# icl7109-rp2040-precision-meter_2025-05-1.net
KiCad netlist of a schematic drawn in EasyEDA Pro
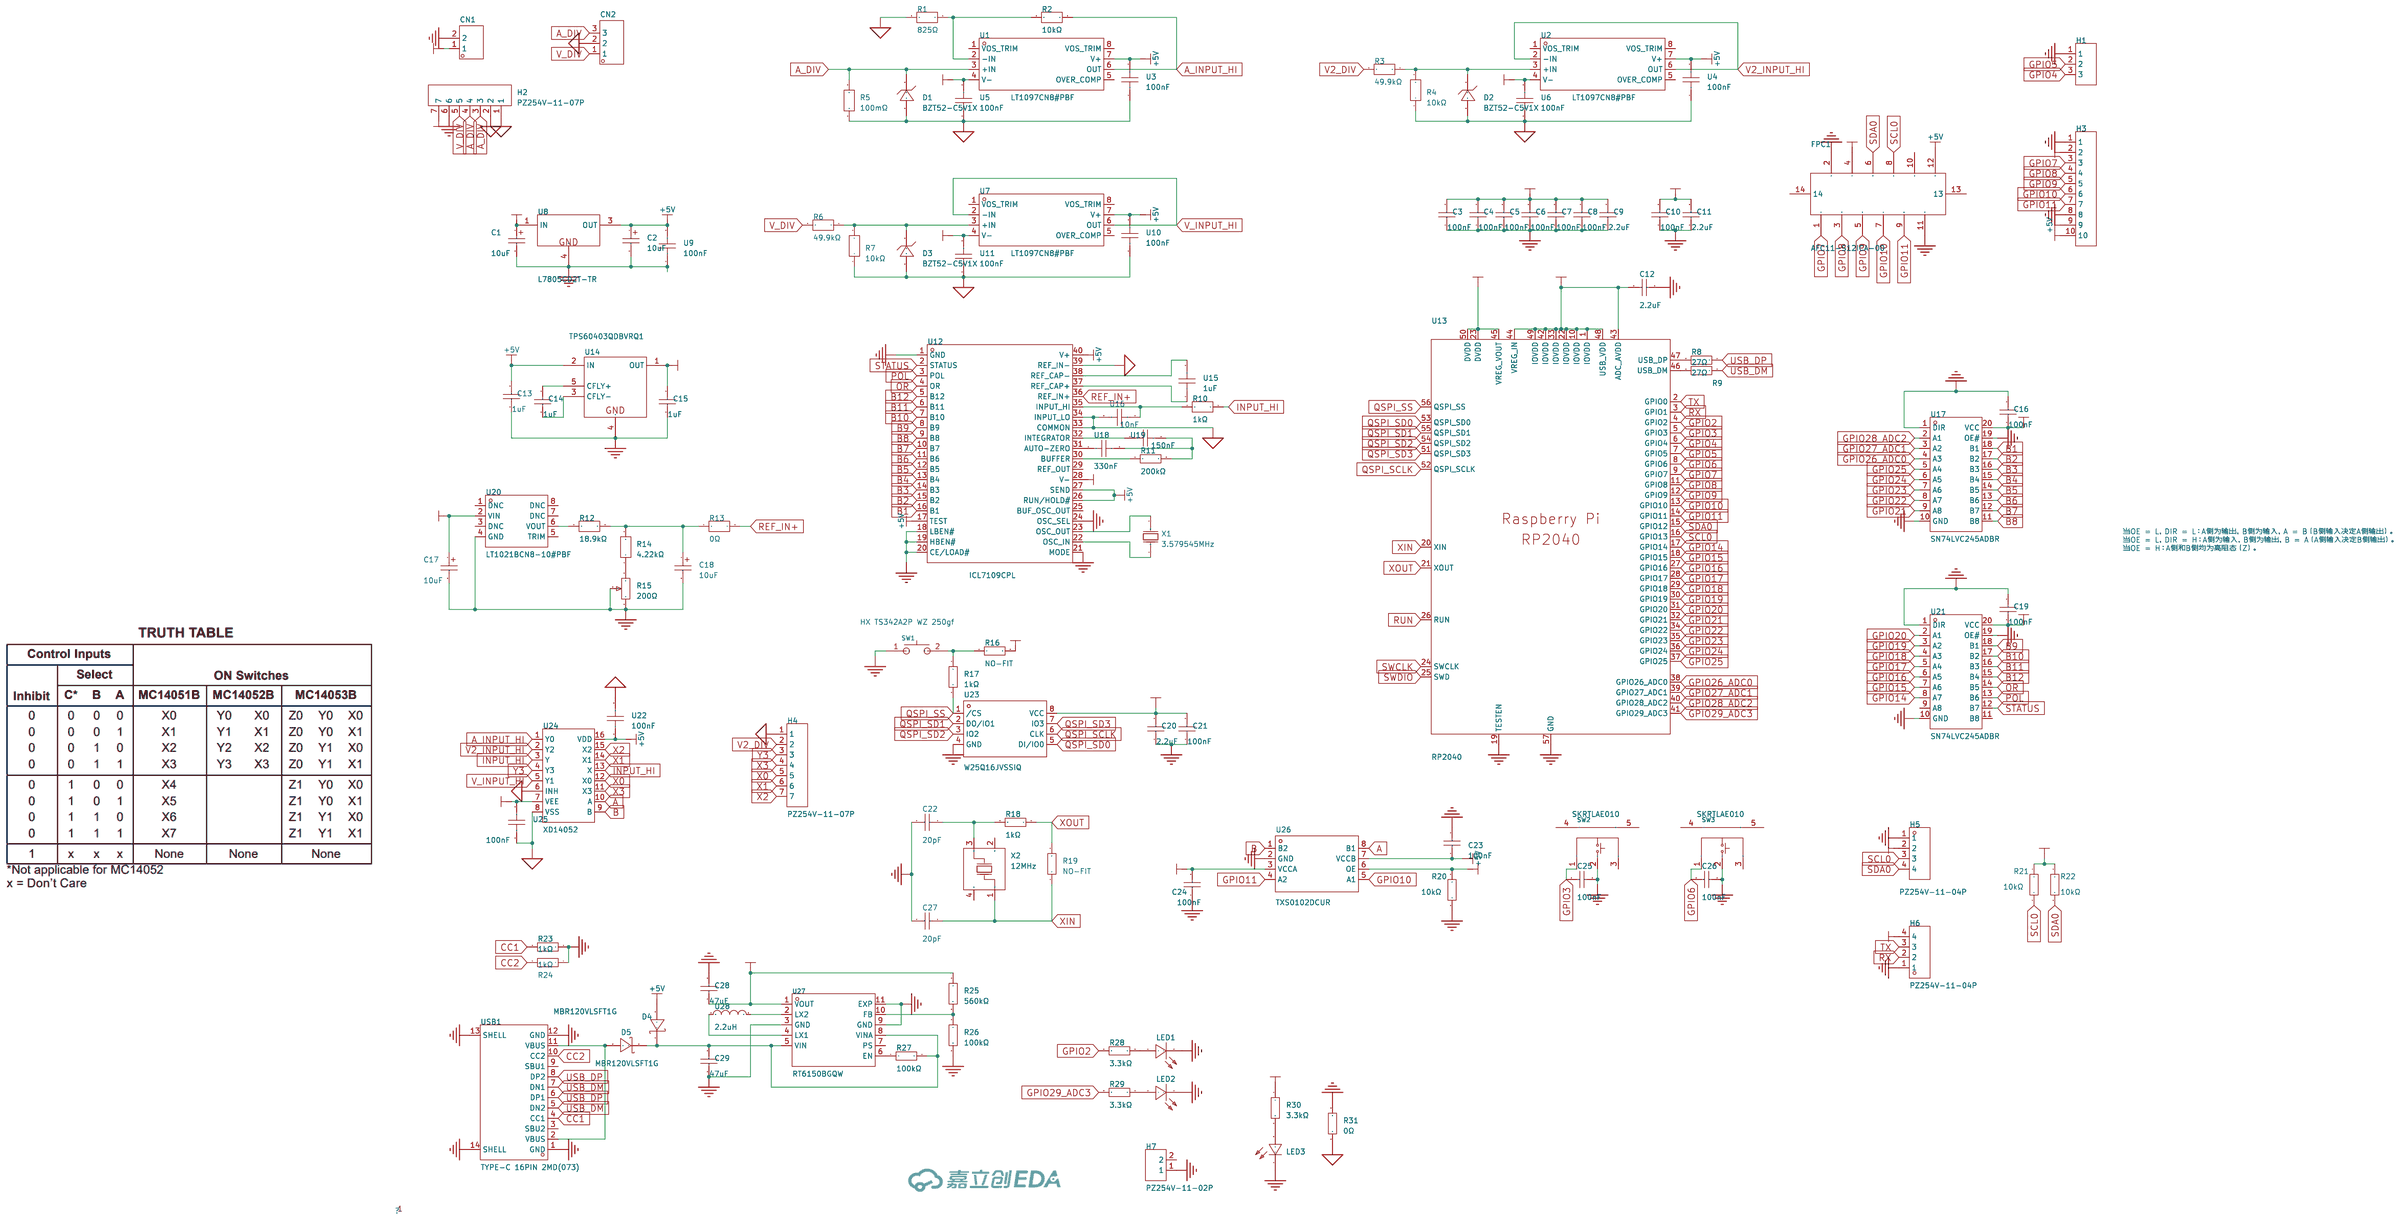
[diagram p0: schematic sheet]

(export (version "E")
  (design (tool "Eeschema 10.0.6"))
  (components
    (comp (ref "C1")
      (value "10uF")
      (footprint "easyedapro:CAP-SMD_L7.3-W4.3-FD")
      (description "容值:47uF;精度:±10%;额定电压:35V;等效串联电阻:600mΩ@100kHz;")
      (fields (field (name "Manufacturer Part") "T491X476K035AT") (field (name "Manufacturer") "KEMET(基美)"))
      (libsource (lib "easyedapro") (part "T491X476K035AT"))
    )
    (comp (ref "C2")
      (value "10uF")
      (footprint "easyedapro:case-b_3528")
      (description "容值:10uF;精度:±10%;额定电压:25V;等效串联电阻:2Ω@100kHz;")
      (fields (field (name "Manufacturer Part") "T491B106K025AT") (field (name "Manufacturer") "KEMET(基美)"))
      (libsource (lib "easyedapro") (part "T491B106K025AT"))
    )
    (comp (ref "C3")
      (value "100nF")
      (footprint "easyedapro:C0805")
      (description "容值:100nF;精度:±10%;额定电压:50V;材质(温度系数):X7R;")
      (fields
        (field (name "Manufacturer Part") "CC0805KRX7R9BB104")
        (field (name "Manufacturer") "YAGEO(国巨)")
      )
      (libsource (lib "easyedapro") (part "CC0805KRX7R9BB104"))
    )
    (comp (ref "C4")
      (value "100nF")
      (footprint "easyedapro:C0805")
      (description "容值:100nF;精度:±10%;额定电压:50V;材质(温度系数):X7R;")
      (fields
        (field (name "Manufacturer Part") "CC0805KRX7R9BB104")
        (field (name "Manufacturer") "YAGEO(国巨)")
      )
      (libsource (lib "easyedapro") (part "CC0805KRX7R9BB104"))
    )
    (comp (ref "C5")
      (value "100nF")
      (footprint "easyedapro:C0805")
      (description "容值:100nF;精度:±10%;额定电压:50V;材质(温度系数):X7R;")
      (fields
        (field (name "Manufacturer Part") "CC0805KRX7R9BB104")
        (field (name "Manufacturer") "YAGEO(国巨)")
      )
      (libsource (lib "easyedapro") (part "CC0805KRX7R9BB104"))
    )
    (comp (ref "C6")
      (value "100nF")
      (footprint "easyedapro:C0805")
      (description "容值:100nF;精度:±10%;额定电压:50V;材质(温度系数):X7R;")
      (fields
        (field (name "Manufacturer Part") "CC0805KRX7R9BB104")
        (field (name "Manufacturer") "YAGEO(国巨)")
      )
      (libsource (lib "easyedapro") (part "CC0805KRX7R9BB104"))
    )
    (comp (ref "C7")
      (value "100nF")
      (footprint "easyedapro:C0805")
      (description "容值:100nF;精度:±10%;额定电压:50V;材质(温度系数):X7R;")
      (fields
        (field (name "Manufacturer Part") "CC0805KRX7R9BB104")
        (field (name "Manufacturer") "YAGEO(国巨)")
      )
      (libsource (lib "easyedapro") (part "CC0805KRX7R9BB104"))
    )
    (comp (ref "C8")
      (value "100nF")
      (footprint "easyedapro:C0805")
      (description "容值:100nF;精度:±10%;额定电压:50V;材质(温度系数):X7R;")
      (fields
        (field (name "Manufacturer Part") "CC0805KRX7R9BB104")
        (field (name "Manufacturer") "YAGEO(国巨)")
      )
      (libsource (lib "easyedapro") (part "CC0805KRX7R9BB104"))
    )
    (comp (ref "C9")
      (value "2.2uF")
      (footprint "easyedapro:C0805")
      (description "容值:100nF;精度:±10%;额定电压:50V;材质(温度系数):X7R;")
      (fields
        (field (name "Manufacturer Part") "CC0805KRX7R9BB104")
        (field (name "Manufacturer") "YAGEO(国巨)")
      )
      (libsource (lib "easyedapro") (part "CC0805KRX7R9BB104"))
    )
    (comp (ref "C10")
      (value "100nF")
      (footprint "easyedapro:C0805")
      (description "容值:100nF;精度:±10%;额定电压:50V;材质(温度系数):X7R;")
      (fields
        (field (name "Manufacturer Part") "CC0805KRX7R9BB104")
        (field (name "Manufacturer") "YAGEO(国巨)")
      )
      (libsource (lib "easyedapro") (part "CC0805KRX7R9BB104"))
    )
    (comp (ref "C11")
      (value "2.2uF")
      (footprint "easyedapro:C0805")
      (description "容值:100nF;精度:±10%;额定电压:50V;材质(温度系数):X7R;")
      (fields
        (field (name "Manufacturer Part") "CC0805KRX7R9BB104")
        (field (name "Manufacturer") "YAGEO(国巨)")
      )
      (libsource (lib "easyedapro") (part "CC0805KRX7R9BB104"))
    )
    (comp (ref "C12")
      (value "2.2uF")
      (footprint "easyedapro:C0805")
      (description "容值:100nF;精度:±10%;额定电压:50V;材质(温度系数):X7R;")
      (fields
        (field (name "Manufacturer Part") "CC0805KRX7R9BB104")
        (field (name "Manufacturer") "YAGEO(国巨)")
      )
      (libsource (lib "easyedapro") (part "CC0805KRX7R9BB104"))
    )
    (comp (ref "C13")
      (value "1uF")
      (footprint "easyedapro:C0805")
      (description "容值:100nF;精度:±10%;额定电压:50V;材质(温度系数):X7R;")
      (fields
        (field (name "Manufacturer Part") "CC0805KRX7R9BB104")
        (field (name "Manufacturer") "YAGEO(国巨)")
      )
      (libsource (lib "easyedapro") (part "CC0805KRX7R9BB104"))
    )
    (comp (ref "C14")
      (value "1uF")
      (footprint "easyedapro:C0805")
      (description "容值:100nF;精度:±10%;额定电压:50V;材质(温度系数):X7R;")
      (fields
        (field (name "Manufacturer Part") "CC0805KRX7R9BB104")
        (field (name "Manufacturer") "YAGEO(国巨)")
      )
      (libsource (lib "easyedapro") (part "CC0805KRX7R9BB104"))
    )
    (comp (ref "C15")
      (value "1uF")
      (footprint "easyedapro:C0805")
      (description "容值:100nF;精度:±10%;额定电压:50V;材质(温度系数):X7R;")
      (fields
        (field (name "Manufacturer Part") "CC0805KRX7R9BB104")
        (field (name "Manufacturer") "YAGEO(国巨)")
      )
      (libsource (lib "easyedapro") (part "CC0805KRX7R9BB104"))
    )
    (comp (ref "C16")
      (value "100nF")
      (footprint "easyedapro:C0805")
      (description "容值:100nF;精度:±10%;额定电压:50V;材质(温度系数):X7R;")
      (fields
        (field (name "Manufacturer Part") "CC0805KRX7R9BB104")
        (field (name "Manufacturer") "YAGEO(国巨)")
      )
      (libsource (lib "easyedapro") (part "CC0805KRX7R9BB104"))
    )
    (comp (ref "C17")
      (value "10uF")
      (footprint "easyedapro:CAP-SMD_L7.3-W4.3-FD")
      (description "容值:47uF;精度:±10%;额定电压:35V;等效串联电阻:600mΩ@100kHz;")
      (fields (field (name "Manufacturer Part") "T491X476K035AT") (field (name "Manufacturer") "KEMET(基美)"))
      (libsource (lib "easyedapro") (part "T491X476K035AT"))
    )
    (comp (ref "C18")
      (value "10uF")
      (footprint "easyedapro:case-b_3528")
      (description "容值:10uF;精度:±10%;额定电压:25V;等效串联电阻:2Ω@100kHz;")
      (fields (field (name "Manufacturer Part") "T491B106K025AT") (field (name "Manufacturer") "KEMET(基美)"))
      (libsource (lib "easyedapro") (part "T491B106K025AT"))
    )
    (comp (ref "C19")
      (value "100nF")
      (footprint "easyedapro:C0805")
      (description "容值:100nF;精度:±10%;额定电压:50V;材质(温度系数):X7R;")
      (fields
        (field (name "Manufacturer Part") "CC0805KRX7R9BB104")
        (field (name "Manufacturer") "YAGEO(国巨)")
      )
      (libsource (lib "easyedapro") (part "CC0805KRX7R9BB104"))
    )
    (comp (ref "C20")
      (value "2.2uF")
      (footprint "easyedapro:C0805")
      (description "容值:100nF;精度:±10%;额定电压:50V;材质(温度系数):X7R;")
      (fields
        (field (name "Manufacturer Part") "CC0805KRX7R9BB104")
        (field (name "Manufacturer") "YAGEO(国巨)")
      )
      (libsource (lib "easyedapro") (part "CC0805KRX7R9BB104"))
    )
    (comp (ref "C21")
      (value "100nF")
      (footprint "easyedapro:C0805")
      (description "容值:100nF;精度:±10%;额定电压:50V;材质(温度系数):X7R;")
      (fields
        (field (name "Manufacturer Part") "CC0805KRX7R9BB104")
        (field (name "Manufacturer") "YAGEO(国巨)")
      )
      (libsource (lib "easyedapro") (part "CC0805KRX7R9BB104"))
    )
    (comp (ref "C22")
      (value "20pF")
      (footprint "easyedapro:C0805")
      (description "容值:100nF;精度:±10%;额定电压:50V;材质(温度系数):X7R;")
      (fields
        (field (name "Manufacturer Part") "CC0805KRX7R9BB104")
        (field (name "Manufacturer") "YAGEO(国巨)")
      )
      (libsource (lib "easyedapro") (part "CC0805KRX7R9BB104"))
    )
    (comp (ref "C23")
      (value "100nF")
      (footprint "easyedapro:C0805")
      (description "容值:100nF;精度:±10%;额定电压:50V;材质(温度系数):X7R;")
      (fields (field (name "Manufacturer Part") "0805B104K500NT") (field (name "Manufacturer") "FH(风华)"))
      (libsource (lib "easyedapro") (part "0805B104K500NT"))
    )
    (comp (ref "C24")
      (value "100nF")
      (footprint "easyedapro:C0805")
      (description "容值:100nF;精度:±10%;额定电压:50V;材质(温度系数):X7R;")
      (fields (field (name "Manufacturer Part") "0805B104K500NT") (field (name "Manufacturer") "FH(风华)"))
      (libsource (lib "easyedapro") (part "0805B104K500NT"))
    )
    (comp (ref "C25")
      (value "100nF")
      (footprint "easyedapro:C0805")
      (description "容值:100nF;精度:±10%;额定电压:50V;材质(温度系数):X7R;")
      (fields
        (field (name "Manufacturer Part") "CC0805KRX7R9BB104")
        (field (name "Manufacturer") "YAGEO(国巨)")
      )
      (libsource (lib "easyedapro") (part "CC0805KRX7R9BB104"))
    )
    (comp (ref "C26")
      (value "100nF")
      (footprint "easyedapro:C0805")
      (description "容值:100nF;精度:±10%;额定电压:50V;材质(温度系数):X7R;")
      (fields
        (field (name "Manufacturer Part") "CC0805KRX7R9BB104")
        (field (name "Manufacturer") "YAGEO(国巨)")
      )
      (libsource (lib "easyedapro") (part "CC0805KRX7R9BB104"))
    )
    (comp (ref "C27")
      (value "20pF")
      (footprint "easyedapro:C0805")
      (description "容值:100nF;精度:±10%;额定电压:50V;材质(温度系数):X7R;")
      (fields
        (field (name "Manufacturer Part") "CC0805KRX7R9BB104")
        (field (name "Manufacturer") "YAGEO(国巨)")
      )
      (libsource (lib "easyedapro") (part "CC0805KRX7R9BB104"))
    )
    (comp (ref "C28")
      (value "47uF")
      (footprint "easyedapro:C0805")
      (description "容值:100nF;精度:±10%;额定电压:50V;材质(温度系数):X7R;")
      (fields
        (field (name "Manufacturer Part") "CC0805KRX7R9BB104")
        (field (name "Manufacturer") "YAGEO(国巨)")
      )
      (libsource (lib "easyedapro") (part "CC0805KRX7R9BB104"))
    )
    (comp (ref "C29")
      (value "47uF")
      (footprint "easyedapro:C0805")
      (description "容值:100nF;精度:±10%;额定电压:50V;材质(温度系数):X7R;")
      (fields
        (field (name "Manufacturer Part") "CC0805KRX7R9BB104")
        (field (name "Manufacturer") "YAGEO(国巨)")
      )
      (libsource (lib "easyedapro") (part "CC0805KRX7R9BB104"))
    )
    (comp (ref "CN1")
      (value "WJ15EDGVC-3.81-2P")
      (footprint "easyedapro:CONN-TH_WJ15EDGVC-3.81-2P")
      (fields (field (name "Manufacturer") "KANGNEX(康奈克斯电气)"))
      (libsource (lib "easyedapro") (part "WJ15EDGVC-3.81-2P"))
    )
    (comp (ref "CN2")
      (value "WJ15EDGVC-3.81-3P")
      (footprint "easyedapro:CONN-TH_3P-P3.81_WJ15EDGVC-3.81-3P")
      (fields (field (name "Manufacturer") "KANGNEX(康奈克斯电气)"))
      (libsource (lib "easyedapro") (part "WJ15EDGVC-3.81-3P"))
    )
    (comp (ref "D1")
      (value "BZT52-C5V1X")
      (footprint "easyedapro:SOD-123_L2.7-W1.6-LS3.7-RD")
      (description "稳压值(标称值):5.1V;功率(Pd):350mW;")
      (fields (field (name "Manufacturer") "Nexperia(安世)"))
      (libsource (lib "easyedapro") (part "BZT52-C5V1X"))
    )
    (comp (ref "D2")
      (value "BZT52-C5V1X")
      (footprint "easyedapro:SOD-123_L2.7-W1.6-LS3.7-RD")
      (description "稳压值(标称值):5.1V;功率(Pd):350mW;")
      (fields (field (name "Manufacturer") "Nexperia(安世)"))
      (libsource (lib "easyedapro") (part "BZT52-C5V1X"))
    )
    (comp (ref "D3")
      (value "BZT52-C5V1X")
      (footprint "easyedapro:SOD-123_L2.7-W1.6-LS3.7-RD")
      (description "稳压值(标称值):5.1V;功率(Pd):350mW;")
      (fields (field (name "Manufacturer") "Nexperia(安世)"))
      (libsource (lib "easyedapro") (part "BZT52-C5V1X"))
    )
    (comp (ref "D4")
      (value "MBR120VLSFT1G")
      (footprint "easyedapro:SOD-123F_L2.8-W1.8-LS3.7-RD")
      (description "正向压降(Vf):300mV@1A;直流反向耐压(Vr):20V;平均整流电流(Io):1A;")
      (fields (field (name "Manufacturer") "onsemi(安森美)"))
      (libsource (lib "easyedapro") (part "MBR120VLSFT1G"))
    )
    (comp (ref "D5")
      (value "MBR120VLSFT1G")
      (footprint "easyedapro:SOD-123F_L2.8-W1.8-LS3.7-RD")
      (description "正向压降(Vf):300mV@1A;直流反向耐压(Vr):20V;平均整流电流(Io):1A;")
      (fields (field (name "Manufacturer") "onsemi(安森美)"))
      (libsource (lib "easyedapro") (part "MBR120VLSFT1G"))
    )
    (comp (ref "FPC1")
      (value "AFC11-S12ICA-00")
      (footprint "easyedapro:CONN-SMD-12P_AFC11-S12ICA-00")
      (description "锁定特性:抽屉式;触点类型:单侧触点/垂直;触点数量:12P;间距:0.5mm;安装类型:立贴;")
      (fields (field (name "Manufacturer") "JS(钜硕电子)"))
      (libsource (lib "easyedapro") (part "AFC11-S12ICA-00"))
    )
    (comp (ref "H1")
      (value "PZ254V-11-03P")
      (footprint "easyedapro:HDR-TH_3P-P2.54-V-M")
      (fields (field (name "Manufacturer") "XFCN(兴飞)"))
      (libsource (lib "easyedapro") (part "PZ254V-11-03P_C2937625"))
    )
    (comp (ref "H2")
      (value "PZ254V-11-07P")
      (footprint "easyedapro:HDR-TH_7P-P2.54-V-M")
      (fields (field (name "Manufacturer") "XFCN(兴飞)"))
      (libsource (lib "easyedapro") (part "PZ254V-11-07P"))
    )
    (comp (ref "H3")
      (value "PZ254V-11-10P")
      (footprint "easyedapro:HDR-TH_10P-P2.54-V-M")
      (fields (field (name "Manufacturer") "XFCN(兴飞)"))
      (libsource (lib "easyedapro") (part "PZ254V-11-10P"))
    )
    (comp (ref "H4")
      (value "PZ254V-11-07P")
      (footprint "easyedapro:HDR-TH_7P-P2.54-V-M")
      (fields (field (name "Manufacturer") "XFCN(兴飞)"))
      (libsource (lib "easyedapro") (part "PZ254V-11-07P"))
    )
    (comp (ref "H5")
      (value "PZ254V-11-04P")
      (footprint "easyedapro:HDR-TH_4P-P2.54-V-M")
      (fields (field (name "Manufacturer") "XFCN(兴飞)"))
      (libsource (lib "easyedapro") (part "PZ254V-11-04P_C2691448"))
    )
    (comp (ref "H6")
      (value "PZ254V-11-04P")
      (footprint "easyedapro:HDR-TH_4P-P2.54-V-M")
      (fields (field (name "Manufacturer") "XFCN(兴飞)"))
      (libsource (lib "easyedapro") (part "PZ254V-11-04P_C2691448"))
    )
    (comp (ref "H7")
      (value "PZ254V-11-02P")
      (footprint "easyedapro:HDR-TH_2P-P2.54-V-M")
      (fields (field (name "Manufacturer") "XFCN(兴飞)"))
      (libsource (lib "easyedapro") (part "PZ254V-11-02P"))
    )
    (comp (ref "LED1")
      (value "LTST-C190KSKT")
      (footprint "easyedapro:LED0603-RD")
      (fields (field (name "Manufacturer") "LITEON(光宝)"))
      (libsource (lib "easyedapro") (part "LTST-C190KSKT"))
    )
    (comp (ref "LED2")
      (value "LTST-C190KSKT")
      (footprint "easyedapro:LED0603-RD")
      (fields (field (name "Manufacturer") "LITEON(光宝)"))
      (libsource (lib "easyedapro") (part "LTST-C190KSKT"))
    )
    (comp (ref "LED3")
      (value "NCD0603R1")
      (footprint "easyedapro:LED0603-RD_RED")
      (fields (field (name "Manufacturer") "国星光电"))
      (libsource (lib "easyedapro") (part "FC-DA1608HRK-620D"))
    )
    (comp (ref "R1")
      (value "825Ω")
      (footprint "easyedapro:RES-TH_BD2.7-L6.2-P10.20-D0.4")
      (description "电阻类型:金属膜电阻;阻值:1kΩ;精度:±1%;功率:250mW;温度系数:±100ppm/°C;")
      (fields (field (name "Manufacturer Part") "MF1/4W-1K±1%-ST52") (field (name "Manufacturer") "VO(翔胜)"))
      (libsource (lib "easyedapro") (part "MF1/4W-1K±1%-ST52"))
    )
    (comp (ref "R2")
      (value "10kΩ")
      (footprint "easyedapro:RES-TH_BD2.7-L6.2-P10.20-D0.4")
      (description "电阻类型:金属膜电阻;阻值:1kΩ;精度:±1%;功率:250mW;温度系数:±100ppm/°C;")
      (fields (field (name "Manufacturer Part") "MF1/4W-1K±1%-ST52") (field (name "Manufacturer") "VO(翔胜)"))
      (libsource (lib "easyedapro") (part "MF1/4W-1K±1%-ST52"))
    )
    (comp (ref "R3")
      (value "49.9kΩ")
      (footprint "easyedapro:RES-TH_BD2.7-L6.2-P10.20-D0.4")
      (description "电阻类型:金属膜电阻;阻值:1kΩ;精度:±1%;功率:250mW;温度系数:±100ppm/°C;")
      (fields (field (name "Manufacturer Part") "MF1/4W-1K±1%-ST52") (field (name "Manufacturer") "VO(翔胜)"))
      (libsource (lib "easyedapro") (part "MF1/4W-1K±1%-ST52"))
    )
    (comp (ref "R4")
      (value "10kΩ")
      (footprint "easyedapro:RES-TH_BD2.7-L6.2-P10.20-D0.4")
      (description "电阻类型:金属膜电阻;阻值:1kΩ;精度:±1%;功率:250mW;温度系数:±100ppm/°C;")
      (fields (field (name "Manufacturer Part") "MF1/4W-1K±1%-ST52") (field (name "Manufacturer") "VO(翔胜)"))
      (libsource (lib "easyedapro") (part "MF1/4W-1K±1%-ST52"))
    )
    (comp (ref "R5")
      (value "100mΩ")
      (footprint "easyedapro:RES-SMD_L6.4-W3.2-R2512")
      (description "电阻类型:采样电阻;阻值:100mΩ;精度:±1%;功率:3W;安装方式:贴片;")
      (fields
        (field (name "Manufacturer Part") "HoJLR2512-3W-100mR-1%")
        (field (name "Manufacturer") "Milliohm(毫欧)")
      )
      (libsource (lib "easyedapro") (part "HOJLR2512-3W-100MR-1%"))
    )
    (comp (ref "R6")
      (value "49.9kΩ")
      (footprint "easyedapro:RES-TH_BD2.7-L6.2-P10.20-D0.4")
      (description "电阻类型:金属膜电阻;阻值:1kΩ;精度:±1%;功率:250mW;温度系数:±100ppm/°C;")
      (fields (field (name "Manufacturer Part") "MF1/4W-1K±1%-ST52") (field (name "Manufacturer") "VO(翔胜)"))
      (libsource (lib "easyedapro") (part "MF1/4W-1K±1%-ST52"))
    )
    (comp (ref "R7")
      (value "10kΩ")
      (footprint "easyedapro:RES-TH_BD2.7-L6.2-P10.20-D0.4")
      (description "电阻类型:金属膜电阻;阻值:1kΩ;精度:±1%;功率:250mW;温度系数:±100ppm/°C;")
      (fields (field (name "Manufacturer Part") "MF1/4W-1K±1%-ST52") (field (name "Manufacturer") "VO(翔胜)"))
      (libsource (lib "easyedapro") (part "MF1/4W-1K±1%-ST52"))
    )
    (comp (ref "R8")
      (value "27Ω")
      (footprint "easyedapro:r0805")
      (description "电阻类型:厚膜电阻;阻值:100Ω;精度:±1%;功率:125mW;最大工作电压:150V;温度系数:±100ppm/°C;")
      (fields
        (field (name "Manufacturer Part") "0805W8F1000T5E")
        (field (name "Manufacturer") "UNI-ROYAL(厚声)")
      )
      (libsource (lib "easyedapro") (part "0805W8F1000T5E"))
    )
    (comp (ref "R9")
      (value "27Ω")
      (footprint "easyedapro:r0805")
      (description "电阻类型:厚膜电阻;阻值:100Ω;精度:±1%;功率:125mW;最大工作电压:150V;温度系数:±100ppm/°C;")
      (fields
        (field (name "Manufacturer Part") "0805W8F1000T5E")
        (field (name "Manufacturer") "UNI-ROYAL(厚声)")
      )
      (libsource (lib "easyedapro") (part "0805W8F1000T5E"))
    )
    (comp (ref "R10")
      (value "1kΩ")
      (footprint "easyedapro:RES-TH_BD2.7-L6.2-P10.20-D0.4")
      (description "电阻类型:金属膜电阻;阻值:1kΩ;精度:±1%;功率:250mW;温度系数:±100ppm/°C;")
      (fields (field (name "Manufacturer Part") "MF1/4W-1K±1%-ST52") (field (name "Manufacturer") "VO(翔胜)"))
      (libsource (lib "easyedapro") (part "MF1/4W-1K±1%-ST52"))
    )
    (comp (ref "R11")
      (value "200kΩ")
      (footprint "easyedapro:R1206")
      (description "电阻类型:厚膜电阻;阻值:0Ω;精度:±1%;功率:250mW;最大工作电压:200V;温度系数:±800ppm/°C;")
      (fields
        (field (name "Manufacturer Part") "1206W4F0000T5E")
        (field (name "Manufacturer") "UNI-ROYAL(厚声)")
      )
      (libsource (lib "easyedapro") (part "1206W4F0000T5E"))
    )
    (comp (ref "R12")
      (value "18.9kΩ")
      (footprint "easyedapro:RES-TH_BD2.7-L6.2-P10.20-D0.4")
      (description "电阻类型:金属膜电阻;阻值:1kΩ;精度:±1%;功率:250mW;温度系数:±100ppm/°C;")
      (fields (field (name "Manufacturer Part") "MF1/4W-1K±1%-ST52") (field (name "Manufacturer") "VO(翔胜)"))
      (libsource (lib "easyedapro") (part "MF1/4W-1K±1%-ST52"))
    )
    (comp (ref "R13")
      (value "0Ω")
      (footprint "easyedapro:RES-TH_BD2.7-L6.2-P10.20-D0.4")
      (description "电阻类型:金属膜电阻;阻值:1kΩ;精度:±1%;功率:250mW;温度系数:±100ppm/°C;")
      (fields (field (name "Manufacturer Part") "MF1/4W-1K±1%-ST52") (field (name "Manufacturer") "VO(翔胜)"))
      (libsource (lib "easyedapro") (part "MF1/4W-1K±1%-ST52"))
    )
    (comp (ref "R14")
      (value "4.22kΩ")
      (footprint "easyedapro:RES-TH_BD2.7-L6.2-P10.20-D0.4")
      (description "电阻类型:金属膜电阻;阻值:1kΩ;精度:±1%;功率:250mW;温度系数:±100ppm/°C;")
      (fields (field (name "Manufacturer Part") "MF1/4W-1K±1%-ST52") (field (name "Manufacturer") "VO(翔胜)"))
      (libsource (lib "easyedapro") (part "MF1/4W-1K±1%-ST52"))
    )
    (comp (ref "R15")
      (value "200Ω")
      (footprint "easyedapro:RES-ADJ-TH_3P-L9.5-W9.5-P2.54-BR-BS")
      (description "阻值:10kΩ;精度:±10%;功率:500mW;温度系数:±100ppm/°C;")
      (fields (field (name "Manufacturer Part") "3386P-1-103LF") (field (name "Manufacturer") "BOURNS"))
      (libsource (lib "easyedapro") (part "3386P-1-103LF"))
    )
    (comp (ref "R16")
      (value "NO-FIT")
      (footprint "easyedapro:r0805")
      (description "电阻类型:厚膜电阻;阻值:100Ω;精度:±1%;功率:125mW;最大工作电压:150V;温度系数:±100ppm/°C;")
      (fields
        (field (name "Manufacturer Part") "0805W8F1000T5E")
        (field (name "Manufacturer") "UNI-ROYAL(厚声)")
      )
      (libsource (lib "easyedapro") (part "0805W8F1000T5E"))
    )
    (comp (ref "R17")
      (value "1kΩ")
      (footprint "easyedapro:r0805")
      (description "电阻类型:厚膜电阻;阻值:100Ω;精度:±1%;功率:125mW;最大工作电压:150V;温度系数:±100ppm/°C;")
      (fields
        (field (name "Manufacturer Part") "0805W8F1000T5E")
        (field (name "Manufacturer") "UNI-ROYAL(厚声)")
      )
      (libsource (lib "easyedapro") (part "0805W8F1000T5E"))
    )
    (comp (ref "R18")
      (value "1kΩ")
      (footprint "easyedapro:r0805")
      (description "电阻类型:厚膜电阻;阻值:100Ω;精度:±1%;功率:125mW;最大工作电压:150V;温度系数:±100ppm/°C;")
      (fields
        (field (name "Manufacturer Part") "0805W8F1000T5E")
        (field (name "Manufacturer") "UNI-ROYAL(厚声)")
      )
      (libsource (lib "easyedapro") (part "0805W8F1000T5E"))
    )
    (comp (ref "R19")
      (value "NO-FIT")
      (footprint "easyedapro:r0805")
      (description "电阻类型:厚膜电阻;阻值:100Ω;精度:±1%;功率:125mW;最大工作电压:150V;温度系数:±100ppm/°C;")
      (fields
        (field (name "Manufacturer Part") "0805W8F1000T5E")
        (field (name "Manufacturer") "UNI-ROYAL(厚声)")
      )
      (libsource (lib "easyedapro") (part "0805W8F1000T5E"))
    )
    (comp (ref "R20")
      (value "10kΩ")
      (footprint "easyedapro:r0805")
      (description "电阻类型:厚膜电阻;阻值:10kΩ;精度:±1%;功率:125mW;最大工作电压:150V;温度系数:±100ppm/°C;")
      (fields
        (field (name "Manufacturer Part") "0805W8F1002T5E")
        (field (name "Manufacturer") "UNI-ROYAL(厚声)")
      )
      (libsource (lib "easyedapro") (part "0805W8F1002T5E"))
    )
    (comp (ref "R21")
      (value "10kΩ")
      (footprint "easyedapro:r0805")
      (description "电阻类型:厚膜电阻;阻值:10kΩ;精度:±1%;功率:125mW;最大工作电压:150V;温度系数:±100ppm/°C;")
      (fields
        (field (name "Manufacturer Part") "0805W8F1002T5E")
        (field (name "Manufacturer") "UNI-ROYAL(厚声)")
      )
      (libsource (lib "easyedapro") (part "0805W8F1002T5E"))
    )
    (comp (ref "R22")
      (value "10kΩ")
      (footprint "easyedapro:r0805")
      (description "电阻类型:厚膜电阻;阻值:10kΩ;精度:±1%;功率:125mW;最大工作电压:150V;温度系数:±100ppm/°C;")
      (fields
        (field (name "Manufacturer Part") "0805W8F1002T5E")
        (field (name "Manufacturer") "UNI-ROYAL(厚声)")
      )
      (libsource (lib "easyedapro") (part "0805W8F1002T5E"))
    )
    (comp (ref "R23")
      (value "1kΩ")
      (footprint "easyedapro:r0805")
      (description "电阻类型:厚膜电阻;阻值:100Ω;精度:±1%;功率:125mW;最大工作电压:150V;温度系数:±100ppm/°C;")
      (fields
        (field (name "Manufacturer Part") "0805W8F1000T5E")
        (field (name "Manufacturer") "UNI-ROYAL(厚声)")
      )
      (libsource (lib "easyedapro") (part "0805W8F1000T5E"))
    )
    (comp (ref "R24")
      (value "1kΩ")
      (footprint "easyedapro:r0805")
      (description "电阻类型:厚膜电阻;阻值:100Ω;精度:±1%;功率:125mW;最大工作电压:150V;温度系数:±100ppm/°C;")
      (fields
        (field (name "Manufacturer Part") "0805W8F1000T5E")
        (field (name "Manufacturer") "UNI-ROYAL(厚声)")
      )
      (libsource (lib "easyedapro") (part "0805W8F1000T5E"))
    )
    (comp (ref "R25")
      (value "560kΩ")
      (footprint "easyedapro:r0805")
      (description "电阻类型:厚膜电阻;阻值:100Ω;精度:±1%;功率:125mW;最大工作电压:150V;温度系数:±100ppm/°C;")
      (fields
        (field (name "Manufacturer Part") "0805W8F1000T5E")
        (field (name "Manufacturer") "UNI-ROYAL(厚声)")
      )
      (libsource (lib "easyedapro") (part "0805W8F1000T5E"))
    )
    (comp (ref "R26")
      (value "100kΩ")
      (footprint "easyedapro:r0805")
      (description "电阻类型:厚膜电阻;阻值:100Ω;精度:±1%;功率:125mW;最大工作电压:150V;温度系数:±100ppm/°C;")
      (fields
        (field (name "Manufacturer Part") "0805W8F1000T5E")
        (field (name "Manufacturer") "UNI-ROYAL(厚声)")
      )
      (libsource (lib "easyedapro") (part "0805W8F1000T5E"))
    )
    (comp (ref "R27")
      (value "100kΩ")
      (footprint "easyedapro:r0805")
      (description "电阻类型:厚膜电阻;阻值:100Ω;精度:±1%;功率:125mW;最大工作电压:150V;温度系数:±100ppm/°C;")
      (fields
        (field (name "Manufacturer Part") "0805W8F1000T5E")
        (field (name "Manufacturer") "UNI-ROYAL(厚声)")
      )
      (libsource (lib "easyedapro") (part "0805W8F1000T5E"))
    )
    (comp (ref "R28")
      (value "3.3kΩ")
      (footprint "easyedapro:r0805")
      (description "电阻类型:厚膜电阻;阻值:100Ω;精度:±1%;功率:125mW;最大工作电压:150V;温度系数:±100ppm/°C;")
      (fields
        (field (name "Manufacturer Part") "0805W8F1000T5E")
        (field (name "Manufacturer") "UNI-ROYAL(厚声)")
      )
      (libsource (lib "easyedapro") (part "0805W8F1000T5E"))
    )
    (comp (ref "R29")
      (value "3.3kΩ")
      (footprint "easyedapro:r0805")
      (description "电阻类型:厚膜电阻;阻值:100Ω;精度:±1%;功率:125mW;最大工作电压:150V;温度系数:±100ppm/°C;")
      (fields
        (field (name "Manufacturer Part") "0805W8F1000T5E")
        (field (name "Manufacturer") "UNI-ROYAL(厚声)")
      )
      (libsource (lib "easyedapro") (part "0805W8F1000T5E"))
    )
    (comp (ref "R30")
      (value "3.3kΩ")
      (footprint "easyedapro:R0402")
      (fields (field (name "Manufacturer Part") "RC0402FR-07470RL") (field (name "Manufacturer") "YAGEO(国巨)"))
      (libsource (lib "easyedapro") (part "RC0402FR-07470RL"))
    )
    (comp (ref "R31")
      (value "0Ω")
      (footprint "easyedapro:R1206")
      (description "电阻类型:厚膜电阻;阻值:0Ω;精度:±1%;功率:250mW;最大工作电压:200V;温度系数:±800ppm/°C;")
      (fields
        (field (name "Manufacturer Part") "1206W4F0000T5E")
        (field (name "Manufacturer") "UNI-ROYAL(厚声)")
      )
      (libsource (lib "easyedapro") (part "1206W4F0000T5E"))
    )
    (comp (ref "SW1")
      (value "HX TS342A2P WZ 250gf")
      (footprint "easyedapro:SW-SMD_L4.0-W2.9-LS5.0")
      (description "开关长度:4mm;开关宽度:3mm;开关高度:2.5mm;机械寿命:-;")
      (fields (field (name "Manufacturer") "hanxia(韩下)"))
      (libsource (lib "easyedapro") (part "HX TS342A2P WZ 250GF"))
    )
    (comp (ref "SW2")
      (value "SKRTLAE010")
      (footprint "easyedapro:KEY-SMD_SKRTLAE010")
      (description "电路结构:单刀单掷;按钮形状:圆形按钮;安装方式:卧贴;开关长度:4.5mm;开关宽度:3.4mm;开关高度:3.3mm;触点电流:50mA;额定电压(DC):12V;带灯:-;机械寿命:-;")
      (fields (field (name "Manufacturer") "ALPSALPINE(阿尔卑斯阿尔派)"))
      (libsource (lib "easyedapro") (part "SKRTLAE010"))
    )
    (comp (ref "SW3")
      (value "SKRTLAE010")
      (footprint "easyedapro:KEY-SMD_SKRTLAE010")
      (description "电路结构:单刀单掷;按钮形状:圆形按钮;安装方式:卧贴;开关长度:4.5mm;开关宽度:3.4mm;开关高度:3.3mm;触点电流:50mA;额定电压(DC):12V;带灯:-;机械寿命:-;")
      (fields (field (name "Manufacturer") "ALPSALPINE(阿尔卑斯阿尔派)"))
      (libsource (lib "easyedapro") (part "SKRTLAE010"))
    )
    (comp (ref "U1")
      (value "LT1097CN8#PBF")
      (footprint "easyedapro:PDIP-8_L9.3-W6.4-P2.54-LS7.6-BL")
      (description "放大器数:单路;增益带宽积(GBP):700kHz;压摆率(SR):0.2V/us;输入偏置电流(Ib):40pA;")
      (fields (field (name "Manufacturer") "ADI(亚德诺)"))
      (libsource (lib "easyedapro") (part "LT1097CN8#PBF"))
    )
    (comp (ref "U2")
      (value "LT1097CN8#PBF")
      (footprint "easyedapro:PDIP-8_L9.3-W6.4-P2.54-LS7.6-BL")
      (description "放大器数:单路;增益带宽积(GBP):700kHz;压摆率(SR):0.2V/us;输入偏置电流(Ib):40pA;")
      (fields (field (name "Manufacturer") "ADI(亚德诺)"))
      (libsource (lib "easyedapro") (part "LT1097CN8#PBF"))
    )
    (comp (ref "U3")
      (value "100nF")
      (footprint "easyedapro:CAP-TH_L3.8-W2.5-P5.08-D0.50")
      (description "容值:100nF;精度:±10%;额定电压:50V;温度系数:X7R;")
      (fields (field (name "Manufacturer Part") "A104K15X7RF5UAA") (field (name "Manufacturer") "VISHAY(威世)"))
      (libsource (lib "easyedapro") (part "A104K15X7RF5UAA"))
    )
    (comp (ref "U4")
      (value "100nF")
      (footprint "easyedapro:CAP-TH_L3.8-W2.5-P5.08-D0.50")
      (description "容值:100nF;精度:±10%;额定电压:50V;温度系数:X7R;")
      (fields (field (name "Manufacturer Part") "A104K15X7RF5UAA") (field (name "Manufacturer") "VISHAY(威世)"))
      (libsource (lib "easyedapro") (part "A104K15X7RF5UAA"))
    )
    (comp (ref "U5")
      (value "100nF")
      (footprint "easyedapro:CAP-TH_L3.8-W2.5-P5.08-D0.50")
      (description "容值:100nF;精度:±10%;额定电压:50V;温度系数:X7R;")
      (fields (field (name "Manufacturer Part") "A104K15X7RF5UAA") (field (name "Manufacturer") "VISHAY(威世)"))
      (libsource (lib "easyedapro") (part "A104K15X7RF5UAA"))
    )
    (comp (ref "U6")
      (value "100nF")
      (footprint "easyedapro:CAP-TH_L3.8-W2.5-P5.08-D0.50")
      (description "容值:100nF;精度:±10%;额定电压:50V;温度系数:X7R;")
      (fields (field (name "Manufacturer Part") "A104K15X7RF5UAA") (field (name "Manufacturer") "VISHAY(威世)"))
      (libsource (lib "easyedapro") (part "A104K15X7RF5UAA"))
    )
    (comp (ref "U7")
      (value "LT1097CN8#PBF")
      (footprint "easyedapro:PDIP-8_L9.3-W6.4-P2.54-LS7.6-BL")
      (description "放大器数:单路;增益带宽积(GBP):700kHz;压摆率(SR):0.2V/us;输入偏置电流(Ib):40pA;")
      (fields (field (name "Manufacturer") "ADI(亚德诺)"))
      (libsource (lib "easyedapro") (part "LT1097CN8#PBF"))
    )
    (comp (ref "U8")
      (value "L7805CD2T-TR")
      (footprint "easyedapro:TO-263-2_L10.0-W9.1-P5.08-LS15.2-TL")
      (description "输出类型:固定;最大输入电压:35V;输出电压:5V;输出电流:1.5A;电源纹波抑制比(PSRR):62dB@(120Hz);输出极性:正极;")
      (fields (field (name "Manufacturer") "ST(意法半导体)"))
      (libsource (lib "easyedapro") (part "L7805CD2T-TR"))
    )
    (comp (ref "U9")
      (value "100nF")
      (footprint "easyedapro:CAP-TH_L3.8-W2.5-P5.08-D0.50")
      (description "容值:100nF;精度:±10%;额定电压:50V;温度系数:X7R;")
      (fields (field (name "Manufacturer Part") "A104K15X7RF5UAA") (field (name "Manufacturer") "VISHAY(威世)"))
      (libsource (lib "easyedapro") (part "A104K15X7RF5UAA"))
    )
    (comp (ref "U10")
      (value "100nF")
      (footprint "easyedapro:CAP-TH_L3.8-W2.5-P5.08-D0.50")
      (description "容值:100nF;精度:±10%;额定电压:50V;温度系数:X7R;")
      (fields (field (name "Manufacturer Part") "A104K15X7RF5UAA") (field (name "Manufacturer") "VISHAY(威世)"))
      (libsource (lib "easyedapro") (part "A104K15X7RF5UAA"))
    )
    (comp (ref "U11")
      (value "100nF")
      (footprint "easyedapro:CAP-TH_L3.8-W2.5-P5.08-D0.50")
      (description "容值:100nF;精度:±10%;额定电压:50V;温度系数:X7R;")
      (fields (field (name "Manufacturer Part") "A104K15X7RF5UAA") (field (name "Manufacturer") "VISHAY(威世)"))
      (libsource (lib "easyedapro") (part "A104K15X7RF5UAA"))
    )
    (comp (ref "U12")
      (value "ICL7109CPL")
      (footprint "easyedapro:PDIP-40_L52.3-W13.8-P2.54-LS15.2-BL")
      (description "ICL7109是一款高性能、CMOS、低功耗双斜率积分A/D转换器，设计用于与微处理器轻松接口。")
      (fields (field (name "Manufacturer") "TI(德州仪器)"))
      (libsource (lib "easyedapro") (part "ICL7109CPL"))
    )
    (comp (ref "U13")
      (value "RP2040")
      (footprint "easyedapro:LQFN-56_L7.0-W7.0-P0.4-EP")
      (description "CPU内核:-;RAM总容量:264KB;GPIO端口数量:30;工作电压范围:-;CPU最大主频:133MHz;程序存储器类型:-;应用领域:-;")
      (fields (field (name "Manufacturer") "Raspberry Pi(树莓派)"))
      (libsource (lib "easyedapro") (part "RP2040"))
    )
    (comp (ref "U14")
      (value "TPS60403QDBVRQ1")
      (footprint "easyedapro:SOT-23-5_L3.0-W1.7-P0.95-LS2.8-BR")
      (description "TPS60403-Q1 具有 250kHz 固定频率的汽车类非稳压 60mA 电荷泵电压逆变器")
      (fields (field (name "Manufacturer") "TI(德州仪器)"))
      (libsource (lib "easyedapro") (part "TPS60403QDBVRQ1"))
    )
    (comp (ref "U15")
      (value "1uF")
      (footprint "easyedapro:CAP-TH_L13.0-W5.0-P10.00-D0.6")
      (description "容值:10nF;精度:±10%;电压(AC):310V；380V；350V;等级:X2;")
      (fields (field (name "Manufacturer Part") "PX103K2C1002") (field (name "Manufacturer") "KYET(科雅)"))
      (libsource (lib "easyedapro") (part "PX103K2C1002"))
    )
    (comp (ref "U16")
      (value "10nF")
      (footprint "easyedapro:CAP-TH_L3.8-W2.5-P5.08-D0.50")
      (description "容值:100nF;精度:±10%;额定电压:50V;温度系数:X7R;")
      (fields (field (name "Manufacturer Part") "A104K15X7RF5UAA") (field (name "Manufacturer") "VISHAY(威世)"))
      (libsource (lib "easyedapro") (part "A104K15X7RF5UAA"))
    )
    (comp (ref "U17")
      (value "SN74LVC245ADBR")
      (footprint "easyedapro:SSOP-20_L7.5-W5.2-P0.65-LS8.0-BL")
      (description "SN74LVC245A 具有三态输出的八通道总线收发器")
      (fields (field (name "Manufacturer") "TI(德州仪器)"))
      (libsource (lib "easyedapro") (part "SN74LVC245ADBR"))
    )
    (comp (ref "U18")
      (value "330nF")
      (footprint "easyedapro:CAP-TH_L18.0-W6.0-P15.00-D0.8")
      (description "容值:330nF;精度:±10%;电压(AC):275V；310V；305V;等级:X2;")
      (fields
        (field (name "Manufacturer Part") "MPX334K31D2KN15800")
        (field (name "Manufacturer") "KNSCHA(科尼盛)")
      )
      (libsource (lib "easyedapro") (part "MPX334K31D2KN15800"))
    )
    (comp (ref "U19")
      (value "150nF")
      (footprint "easyedapro:CAP-TH_L13.0-W5.0-P10.00-D0.6")
      (description "容值:10nF;精度:±10%;电压(AC):310V；380V；350V;等级:X2;")
      (fields (field (name "Manufacturer Part") "PX103K2C1002") (field (name "Manufacturer") "KYET(科雅)"))
      (libsource (lib "easyedapro") (part "PX103K2C1002"))
    )
    (comp (ref "U20")
      (value "LT1021BCN8-10#PBF")
      (footprint "easyedapro:PDIP-8_L9.3-W6.4-P2.54-LS7.6-BL")
      (description "输出类型:固定;工作电压:11.5V~40V;输出电压:10V;输出电流:10mA;精度:±0.5%;")
      (fields (field (name "Manufacturer") "ADI(亚德诺)"))
      (libsource (lib "easyedapro") (part "LT1021BCN8-10#PBF"))
    )
    (comp (ref "U21")
      (value "SN74LVC245ADBR")
      (footprint "easyedapro:SSOP-20_L7.5-W5.2-P0.65-LS8.0-BL")
      (description "SN74LVC245A 具有三态输出的八通道总线收发器")
      (fields (field (name "Manufacturer") "TI(德州仪器)"))
      (libsource (lib "easyedapro") (part "SN74LVC245ADBR"))
    )
    (comp (ref "U22")
      (value "100nF")
      (footprint "easyedapro:CAP-TH_L3.8-W2.5-P5.08-D0.50")
      (description "容值:100nF;精度:±10%;额定电压:50V;温度系数:X7R;")
      (fields (field (name "Manufacturer Part") "A104K15X7RF5UAA") (field (name "Manufacturer") "VISHAY(威世)"))
      (libsource (lib "easyedapro") (part "A104K15X7RF5UAA"))
    )
    (comp (ref "U23")
      (value "W25Q16JVSSIQ")
      (footprint "easyedapro:SOIC-8_L5.3-W5.3-P1.27-LS8.0-BL")
      (description "（与C82317为同一颗物料，只是编带方式不一样。）3V 16Mbit Serial Flash Memory with dual/quad SPI")
      (fields (field (name "Manufacturer") "WINBOND(华邦)"))
      (libsource (lib "easyedapro") (part "W25Q16JVSSIQTR"))
    )
    (comp (ref "U24")
      (value "XD14052")
      (footprint "easyedapro:DIP-16_L19.2-W6.6-P2.54-LS7.6-BL")
      (description "接口 - 模拟开关，多路复用器，多路分解器 2 电路 IC 开关 2：4 280 欧姆")
      (fields (field (name "Manufacturer") "XINLUDA(信路达)"))
      (libsource (lib "easyedapro") (part "XD14052"))
    )
    (comp (ref "U25")
      (value "100nF")
      (footprint "easyedapro:CAP-TH_L3.8-W2.5-P5.08-D0.50")
      (description "容值:100nF;精度:±10%;额定电压:50V;温度系数:X7R;")
      (fields (field (name "Manufacturer Part") "A104K15X7RF5UAA") (field (name "Manufacturer") "VISHAY(威世)"))
      (libsource (lib "easyedapro") (part "A104K15X7RF5UAA"))
    )
    (comp (ref "U26")
      (value "TXS0102DCUR")
      (footprint "easyedapro:VSON8_L2.0-W2.3-P0.50-LS3.1-BL")
      (description "数据速率:24Mbps;电压(VCCA):1.65V~3.6V;电压(VCCB):2.3V~5.5V;电路数:1;每个电路通道数:2;")
      (fields (field (name "Manufacturer") "TI(德州仪器)"))
      (libsource (lib "easyedapro") (part "TXS0102DCUR"))
    )
    (comp (ref "U27")
      (value "RT6150BGQW")
      (footprint "easyedapro:WSON-10_L2.5-W2.5-P0.50-BL-EP")
      (description "功能类型:升降压型;输入电压:1.8V~5.5V;输出电压:1.8V~5.5V;输出电流(最大值):800mA;")
      (fields (field (name "Manufacturer") "RICHTEK(立锜)"))
      (libsource (lib "easyedapro") (part "RT6150BGQW"))
    )
    (comp (ref "U28")
      (value "2.2uH")
      (footprint "easyedapro:IND-SMD_L2.5-W2.0-B")
      (description "电感值:2.2uH;精度:±20%;额定电流:3A;饱和电流(Isat):3.8A;类型:一体成型电感;")
      (fields (field (name "Manufacturer Part") "XRIM252012S2R2MBCA") (field (name "Manufacturer") "XR(祥如)"))
      (libsource (lib "easyedapro") (part "XRTC252012S2R2MBCA"))
    )
    (comp (ref "USB1")
      (value "TYPE-C 16PIN 2MD(073)")
      (footprint "easyedapro:USB-C-SMD_TYPE-C-6PIN-2MD-073")
      (description "连接器类型:Type-C;标准:USB 3.1;公母:母;安装方式:卧贴;触点数量:16P;端口数量:1;额定电流 - 电源:5A;工作温度范围:-25°C~+85°C;")
      (fields (field (name "Manufacturer") "SHOU HAN(首韩)"))
      (libsource (lib "easyedapro") (part "TYPE-C 16PIN 2MD(073)"))
    )
    (comp (ref "X1")
      (value "3.579545MHz")
      (footprint "easyedapro:HC-49US_L11.5-W4.5-P4.88")
      (description "晶振类型:直插晶振;频率:3.579545MHz;常温频差:±30ppm;外接负载电容:20pF;频率稳定度(全温):±30ppm;")
      (fields
        (field (name "Manufacturer Part") "XIHCELNANF-3.579545M")
        (field (name "Manufacturer") "TAITIEN(泰艺电子)")
      )
      (libsource (lib "easyedapro") (part "XIHCELNANF-3.579545M"))
    )
    (comp (ref "X2")
      (value "12MHz")
      (footprint "easyedapro:OSC-SMD_4P-L3.2-W2.5-BL")
      (description "晶振类型:贴片晶振;频率:12MHz;常温频差:±10ppm;外接负载电容:20pF;频率稳定度(全温):±20ppm;")
      (fields (field (name "Manufacturer Part") "X322512MSB4SI") (field (name "Manufacturer") "YXC(扬兴晶振)"))
      (libsource (lib "easyedapro") (part "X322512MSB4SI"))
    )
  )
  (nets
    (net (code "1") (name "+1.1V") (class "Default")
      (node (ref "C10") (pin "2") (pinfunction "2_2") (pintype "input"))
      (node (ref "C11") (pin "2") (pinfunction "2_2") (pintype "input"))
      (node (ref "U13") (pin "23") (pinfunction "DVDD_23") (pintype "bidirectional"))
      (node (ref "U13") (pin "45") (pinfunction "VREG_VOUT_45") (pintype "bidirectional"))
      (node (ref "U13") (pin "50") (pinfunction "DVDD_50") (pintype "bidirectional"))
    )
    (net (code "2") (name "+3.3V") (class "Default")
      (node (ref "C12") (pin "2") (pinfunction "2_2") (pintype "input"))
      (node (ref "C16") (pin "1") (pinfunction "1_1") (pintype "input"))
      (node (ref "C19") (pin "1") (pinfunction "1_1") (pintype "input"))
      (node (ref "C20") (pin "2") (pinfunction "2_2") (pintype "input"))
      (node (ref "C21") (pin "2") (pinfunction "2_2") (pintype "input"))
      (node (ref "C24") (pin "2") (pinfunction "2_2") (pintype "input"))
      (node (ref "C28") (pin "1") (pinfunction "1_1") (pintype "input"))
      (node (ref "C3") (pin "2") (pinfunction "2_2") (pintype "input"))
      (node (ref "C4") (pin "2") (pinfunction "2_2") (pintype "input"))
      (node (ref "C5") (pin "2") (pinfunction "2_2") (pintype "input"))
      (node (ref "C6") (pin "2") (pinfunction "2_2") (pintype "input"))
      (node (ref "C7") (pin "2") (pinfunction "2_2") (pintype "input"))
      (node (ref "C8") (pin "2") (pinfunction "2_2") (pintype "input"))
      (node (ref "C9") (pin "2") (pinfunction "2_2") (pintype "input"))
      (node (ref "FPC1") (pin "4") (pinfunction "4_4") (pintype "unspecified"))
      (node (ref "H3") (pin "2") (pinfunction "2_2") (pintype "unspecified"))
      (node (ref "H5") (pin "2") (pinfunction "2_2") (pintype "unspecified"))
      (node (ref "H6") (pin "4") (pinfunction "4_4") (pintype "unspecified"))
      (node (ref "R16") (pin "2") (pinfunction "2_2") (pintype "input"))
      (node (ref "R20") (pin "1") (pinfunction "1_1") (pintype "input"))
      (node (ref "R21") (pin "1") (pinfunction "1_1") (pintype "input"))
      (node (ref "R22") (pin "1") (pinfunction "1_1") (pintype "input"))
      (node (ref "R25") (pin "1") (pinfunction "1_1") (pintype "input"))
      (node (ref "R30") (pin "1") (pinfunction "1_1") (pintype "input"))
      (node (ref "U13") (pin "1") (pinfunction "IOVDD_1") (pintype "bidirectional"))
      (node (ref "U13") (pin "10") (pinfunction "IOVDD_10") (pintype "bidirectional"))
      (node (ref "U13") (pin "22") (pinfunction "IOVDD_22") (pintype "bidirectional"))
      (node (ref "U13") (pin "33") (pinfunction "IOVDD_33") (pintype "bidirectional"))
      (node (ref "U13") (pin "42") (pinfunction "IOVDD_42") (pintype "bidirectional"))
      (node (ref "U13") (pin "43") (pinfunction "ADC_AVDD_43") (pintype "bidirectional"))
      (node (ref "U13") (pin "44") (pinfunction "VREG_IN_44") (pintype "bidirectional"))
      (node (ref "U13") (pin "48") (pinfunction "USB_VDD_48") (pintype "bidirectional"))
      (node (ref "U13") (pin "49") (pinfunction "IOVDD_49") (pintype "bidirectional"))
      (node (ref "U17") (pin "20") (pinfunction "VCC_20") (pintype "unspecified"))
      (node (ref "U21") (pin "20") (pinfunction "VCC_20") (pintype "unspecified"))
      (node (ref "U23") (pin "8") (pinfunction "VCC_8") (pintype "unspecified"))
      (node (ref "U26") (pin "3") (pinfunction "VCCA_3") (pintype "unspecified"))
      (node (ref "U26") (pin "6") (pinfunction "OE_6") (pintype "unspecified"))
      (node (ref "U27") (pin "1") (pinfunction "VOUT_1") (pintype "input"))
    )
    (net (code "3") (name "+5V") (class "Default")
      (node (ref "C13") (pin "2") (pinfunction "2_2") (pintype "input"))
      (node (ref "C2") (pin "1") (pinfunction "1_1") (pintype "input"))
      (node (ref "C23") (pin "1") (pinfunction "1_1") (pintype "input"))
      (node (ref "D4") (pin "2") (pinfunction "A_2") (pintype "unspecified"))
      (node (ref "FPC1") (pin "12") (pinfunction "12_12") (pintype "unspecified"))
      (node (ref "H3") (pin "9") (pinfunction "9_9") (pintype "unspecified"))
      (node (ref "U1") (pin "7") (pinfunction "V+_7") (pintype "unspecified"))
      (node (ref "U10") (pin "2") (pinfunction "2_2") (pintype "unspecified"))
      (node (ref "U12") (pin "17") (pinfunction "TEST_17") (pintype "unspecified"))
      (node (ref "U12") (pin "26") (pinfunction "RUN/HOLD#_26") (pintype "unspecified"))
      (node (ref "U12") (pin "27") (pinfunction "SEND_27") (pintype "unspecified"))
      (node (ref "U12") (pin "40") (pinfunction "V+_40") (pintype "unspecified"))
      (node (ref "U14") (pin "2") (pinfunction "IN_2") (pintype "unspecified"))
      (node (ref "U2") (pin "7") (pinfunction "V+_7") (pintype "unspecified"))
      (node (ref "U22") (pin "1") (pinfunction "1_1") (pintype "unspecified"))
      (node (ref "U24") (pin "16") (pinfunction "VDD_16") (pintype "unspecified"))
      (node (ref "U26") (pin "7") (pinfunction "VCCB_7") (pintype "unspecified"))
      (node (ref "U3") (pin "2") (pinfunction "2_2") (pintype "unspecified"))
      (node (ref "U4") (pin "2") (pinfunction "2_2") (pintype "unspecified"))
      (node (ref "U7") (pin "7") (pinfunction "V+_7") (pintype "unspecified"))
      (node (ref "U8") (pin "3") (pinfunction "OUT_3") (pintype "unspecified"))
      (node (ref "U9") (pin "2") (pinfunction "2_2") (pintype "unspecified"))
    )
    (net (code "4") (name "-5V") (class "Default")
      (node (ref "C15") (pin "2") (pinfunction "2_2") (pintype "input"))
      (node (ref "H3") (pin "10") (pinfunction "10_10") (pintype "unspecified"))
      (node (ref "U1") (pin "4") (pinfunction "V-_4") (pintype "unspecified"))
      (node (ref "U11") (pin "2") (pinfunction "2_2") (pintype "unspecified"))
      (node (ref "U12") (pin "28") (pinfunction "V-_28") (pintype "unspecified"))
      (node (ref "U14") (pin "1") (pinfunction "OUT_1") (pintype "unspecified"))
      (node (ref "U2") (pin "4") (pinfunction "V-_4") (pintype "unspecified"))
      (node (ref "U24") (pin "7") (pinfunction "VEE_7") (pintype "unspecified"))
      (node (ref "U25") (pin "2") (pinfunction "2_2") (pintype "unspecified"))
      (node (ref "U5") (pin "2") (pinfunction "2_2") (pintype "unspecified"))
      (node (ref "U6") (pin "2") (pinfunction "2_2") (pintype "unspecified"))
      (node (ref "U7") (pin "4") (pinfunction "V-_4") (pintype "unspecified"))
    )
    (net (code "5") (name "A") (class "Default")
      (node (ref "U24") (pin "10") (pinfunction "A_10") (pintype "unspecified"))
      (node (ref "U26") (pin "8") (pinfunction "B1_8") (pintype "unspecified"))
    )
    (net (code "6") (name "AGND") (class "Default")
      (node (ref "CN2") (pin "2") (pinfunction "2_2") (pintype "unspecified"))
      (node (ref "D1") (pin "2") (pinfunction "2_2") (pintype "unspecified"))
      (node (ref "D2") (pin "2") (pinfunction "2_2") (pintype "unspecified"))
      (node (ref "D3") (pin "2") (pinfunction "2_2") (pintype "unspecified"))
      (node (ref "H2") (pin "1") (pinfunction "1_1") (pintype "unspecified"))
      (node (ref "H2") (pin "2") (pinfunction "2_2") (pintype "unspecified"))
      (node (ref "H4") (pin "1") (pinfunction "1_1") (pintype "unspecified"))
      (node (ref "R1") (pin "2") (pinfunction "2_2") (pintype "unspecified"))
      (node (ref "R31") (pin "1") (pinfunction "1_1") (pintype "input"))
      (node (ref "R4") (pin "1") (pinfunction "1_1") (pintype "unspecified"))
      (node (ref "R5") (pin "1") (pinfunction "1_1") (pintype "unspecified"))
      (node (ref "R7") (pin "1") (pinfunction "1_1") (pintype "unspecified"))
      (node (ref "U10") (pin "1") (pinfunction "1_1") (pintype "unspecified"))
      (node (ref "U11") (pin "1") (pinfunction "1_1") (pintype "unspecified"))
      (node (ref "U12") (pin "33") (pinfunction "COMMON_33") (pintype "unspecified"))
      (node (ref "U12") (pin "34") (pinfunction "INPUT_LO_34") (pintype "unspecified"))
      (node (ref "U12") (pin "39") (pinfunction "REF_IN-_39") (pintype "unspecified"))
      (node (ref "U16") (pin "2") (pinfunction "2_2") (pintype "unspecified"))
      (node (ref "U22") (pin "2") (pinfunction "2_2") (pintype "unspecified"))
      (node (ref "U24") (pin "6") (pinfunction "INH_6") (pintype "unspecified"))
      (node (ref "U24") (pin "8") (pinfunction "VSS_8") (pintype "unspecified"))
      (node (ref "U25") (pin "1") (pinfunction "1_1") (pintype "unspecified"))
      (node (ref "U3") (pin "1") (pinfunction "1_1") (pintype "unspecified"))
      (node (ref "U4") (pin "1") (pinfunction "1_1") (pintype "unspecified"))
      (node (ref "U5") (pin "1") (pinfunction "1_1") (pintype "unspecified"))
      (node (ref "U6") (pin "1") (pinfunction "1_1") (pintype "unspecified"))
    )
    (net (code "7") (name "A_DIV") (class "Default")
      (node (ref "CN2") (pin "3") (pinfunction "3_3") (pintype "unspecified"))
      (node (ref "D1") (pin "1") (pinfunction "1_1") (pintype "unspecified"))
      (node (ref "H2") (pin "3") (pinfunction "3_3") (pintype "unspecified"))
      (node (ref "H2") (pin "4") (pinfunction "4_4") (pintype "unspecified"))
      (node (ref "R5") (pin "2") (pinfunction "2_2") (pintype "unspecified"))
      (node (ref "U1") (pin "3") (pinfunction "+IN_3") (pintype "unspecified"))
    )
    (net (code "8") (name "A_INPUT_HI") (class "Default")
      (node (ref "R2") (pin "1") (pinfunction "1_1") (pintype "unspecified"))
      (node (ref "U1") (pin "6") (pinfunction "OUT_6") (pintype "unspecified"))
      (node (ref "U24") (pin "1") (pinfunction "Y0_1") (pintype "unspecified"))
    )
    (net (code "9") (name "B") (class "Default")
      (node (ref "U24") (pin "9") (pinfunction "B_9") (pintype "unspecified"))
      (node (ref "U26") (pin "1") (pinfunction "B2_1") (pintype "unspecified"))
    )
    (net (code "10") (name "B1") (class "Default")
      (node (ref "U12") (pin "16") (pinfunction "B1_16") (pintype "unspecified"))
      (node (ref "U17") (pin "18") (pinfunction "B1_18") (pintype "unspecified"))
    )
    (net (code "11") (name "B2") (class "Default")
      (node (ref "U12") (pin "15") (pinfunction "B2_15") (pintype "unspecified"))
      (node (ref "U17") (pin "17") (pinfunction "B2_17") (pintype "unspecified"))
    )
    (net (code "12") (name "B3") (class "Default")
      (node (ref "U12") (pin "14") (pinfunction "B3_14") (pintype "unspecified"))
      (node (ref "U17") (pin "16") (pinfunction "B3_16") (pintype "unspecified"))
    )
    (net (code "13") (name "B4") (class "Default")
      (node (ref "U12") (pin "13") (pinfunction "B4_13") (pintype "unspecified"))
      (node (ref "U17") (pin "15") (pinfunction "B4_15") (pintype "unspecified"))
    )
    (net (code "14") (name "B5") (class "Default")
      (node (ref "U12") (pin "12") (pinfunction "B5_12") (pintype "unspecified"))
      (node (ref "U17") (pin "14") (pinfunction "B5_14") (pintype "unspecified"))
    )
    (net (code "15") (name "B6") (class "Default")
      (node (ref "U12") (pin "11") (pinfunction "B6_11") (pintype "unspecified"))
      (node (ref "U17") (pin "13") (pinfunction "B6_13") (pintype "unspecified"))
    )
    (net (code "16") (name "B7") (class "Default")
      (node (ref "U12") (pin "10") (pinfunction "B7_10") (pintype "unspecified"))
      (node (ref "U17") (pin "12") (pinfunction "B7_12") (pintype "unspecified"))
    )
    (net (code "17") (name "B8") (class "Default")
      (node (ref "U12") (pin "9") (pinfunction "B8_9") (pintype "unspecified"))
      (node (ref "U17") (pin "11") (pinfunction "B8_11") (pintype "unspecified"))
    )
    (net (code "18") (name "B9") (class "Default")
      (node (ref "U12") (pin "8") (pinfunction "B9_8") (pintype "unspecified"))
      (node (ref "U21") (pin "18") (pinfunction "B1_18") (pintype "unspecified"))
    )
    (net (code "19") (name "B10") (class "Default")
      (node (ref "U12") (pin "7") (pinfunction "B10_7") (pintype "unspecified"))
      (node (ref "U21") (pin "17") (pinfunction "B2_17") (pintype "unspecified"))
    )
    (net (code "20") (name "B11") (class "Default")
      (node (ref "U12") (pin "6") (pinfunction "B11_6") (pintype "unspecified"))
      (node (ref "U21") (pin "16") (pinfunction "B3_16") (pintype "unspecified"))
    )
    (net (code "21") (name "B12") (class "Default")
      (node (ref "U12") (pin "5") (pinfunction "B12_5") (pintype "unspecified"))
      (node (ref "U21") (pin "15") (pinfunction "B4_15") (pintype "unspecified"))
    )
    (net (code "22") (name "CC1") (class "Default")
      (node (ref "R23") (pin "2") (pinfunction "2_2") (pintype "input"))
      (node (ref "USB1") (pin "4") (pinfunction "CC1_4") (pintype "unspecified"))
    )
    (net (code "23") (name "CC2") (class "Default")
      (node (ref "R24") (pin "2") (pinfunction "2_2") (pintype "input"))
      (node (ref "USB1") (pin "10") (pinfunction "CC2_10") (pintype "unspecified"))
    )
    (net (code "24") (name "GND") (class "Default")
      (node (ref "C1") (pin "2") (pinfunction "2_2") (pintype "input"))
      (node (ref "C10") (pin "1") (pinfunction "1_1") (pintype "input"))
      (node (ref "C11") (pin "1") (pinfunction "1_1") (pintype "input"))
      (node (ref "C12") (pin "1") (pinfunction "1_1") (pintype "input"))
      (node (ref "C13") (pin "1") (pinfunction "1_1") (pintype "input"))
      (node (ref "C15") (pin "1") (pinfunction "1_1") (pintype "input"))
      (node (ref "C16") (pin "2") (pinfunction "2_2") (pintype "input"))
      (node (ref "C17") (pin "2") (pinfunction "2_2") (pintype "input"))
      (node (ref "C18") (pin "2") (pinfunction "2_2") (pintype "input"))
      (node (ref "C19") (pin "2") (pinfunction "2_2") (pintype "input"))
      (node (ref "C2") (pin "2") (pinfunction "2_2") (pintype "input"))
      (node (ref "C20") (pin "1") (pinfunction "1_1") (pintype "input"))
      (node (ref "C21") (pin "1") (pinfunction "1_1") (pintype "input"))
      (node (ref "C22") (pin "2") (pinfunction "2_2") (pintype "input"))
      (node (ref "C23") (pin "2") (pinfunction "2_2") (pintype "input"))
      (node (ref "C24") (pin "1") (pinfunction "1_1") (pintype "input"))
      (node (ref "C25") (pin "1") (pinfunction "1_1") (pintype "input"))
      (node (ref "C26") (pin "1") (pinfunction "1_1") (pintype "input"))
      (node (ref "C27") (pin "2") (pinfunction "2_2") (pintype "input"))
      (node (ref "C28") (pin "2") (pinfunction "2_2") (pintype "input"))
      (node (ref "C29") (pin "1") (pinfunction "1_1") (pintype "input"))
      (node (ref "C3") (pin "1") (pinfunction "1_1") (pintype "input"))
      (node (ref "C4") (pin "1") (pinfunction "1_1") (pintype "input"))
      (node (ref "C5") (pin "1") (pinfunction "1_1") (pintype "input"))
      (node (ref "C6") (pin "1") (pinfunction "1_1") (pintype "input"))
      (node (ref "C7") (pin "1") (pinfunction "1_1") (pintype "input"))
      (node (ref "C8") (pin "1") (pinfunction "1_1") (pintype "input"))
      (node (ref "C9") (pin "1") (pinfunction "1_1") (pintype "input"))
      (node (ref "CN1") (pin "2") (pinfunction "2_2") (pintype "unspecified"))
      (node (ref "FPC1") (pin "11") (pinfunction "11_11") (pintype "unspecified"))
      (node (ref "FPC1") (pin "2") (pinfunction "2_2") (pintype "unspecified"))
      (node (ref "H1") (pin "1") (pinfunction "1_1") (pintype "unspecified"))
      (node (ref "H2") (pin "6") (pinfunction "6_6") (pintype "unspecified"))
      (node (ref "H3") (pin "1") (pinfunction "1_1") (pintype "unspecified"))
      (node (ref "H3") (pin "8") (pinfunction "8_8") (pintype "unspecified"))
      (node (ref "H5") (pin "1") (pinfunction "1_1") (pintype "unspecified"))
      (node (ref "H6") (pin "1") (pinfunction "1_1") (pintype "unspecified"))
      (node (ref "H7") (pin "1") (pinfunction "1_1") (pintype "unspecified"))
      (node (ref "LED1") (pin "1") (pinfunction "-_1") (pintype "unspecified"))
      (node (ref "LED2") (pin "1") (pinfunction "-_1") (pintype "unspecified"))
      (node (ref "LED3") (pin "1") (pinfunction "K_1") (pintype "input"))
      (node (ref "R15") (pin "2") (pinfunction "2_2") (pintype "input"))
      (node (ref "R15") (pin "3") (pinfunction "3_3") (pintype "input"))
      (node (ref "R20") (pin "2") (pinfunction "2_2") (pintype "input"))
      (node (ref "R23") (pin "1") (pinfunction "1_1") (pintype "input"))
      (node (ref "R24") (pin "1") (pinfunction "1_1") (pintype "input"))
      (node (ref "R26") (pin "2") (pinfunction "2_2") (pintype "input"))
      (node (ref "R31") (pin "2") (pinfunction "2_2") (pintype "input"))
      (node (ref "SW1") (pin "1") (pinfunction "1_1") (pintype "input"))
      (node (ref "SW2") (pin "2") (pinfunction "2_2") (pintype "input"))
      (node (ref "SW3") (pin "2") (pinfunction "2_2") (pintype "input"))
      (node (ref "U12") (pin "1") (pinfunction "GND_1") (pintype "unspecified"))
      (node (ref "U12") (pin "18") (pinfunction "LBEN#_18") (pintype "unspecified"))
      (node (ref "U12") (pin "19") (pinfunction "HBEN#_19") (pintype "unspecified"))
      (node (ref "U12") (pin "20") (pinfunction "CE/LOAD#_20") (pintype "unspecified"))
      (node (ref "U12") (pin "21") (pinfunction "MODE_21") (pintype "unspecified"))
      (node (ref "U12") (pin "24") (pinfunction "OSC_SEL_24") (pintype "unspecified"))
      (node (ref "U13") (pin "19") (pinfunction "TESTEN_19") (pintype "unspecified"))
      (node (ref "U13") (pin "57") (pinfunction "GND_57") (pintype "bidirectional"))
      (node (ref "U14") (pin "4") (pinfunction "GND_4") (pintype "unspecified"))
      (node (ref "U17") (pin "1") (pinfunction "DIR_1") (pintype "unspecified"))
      (node (ref "U17") (pin "10") (pinfunction "GND_10") (pintype "unspecified"))
      (node (ref "U17") (pin "19") (pinfunction "OE#_19") (pintype "unspecified"))
      (node (ref "U20") (pin "4") (pinfunction "GND_4") (pintype "unspecified"))
      (node (ref "U21") (pin "1") (pinfunction "DIR_1") (pintype "unspecified"))
      (node (ref "U21") (pin "10") (pinfunction "GND_10") (pintype "unspecified"))
      (node (ref "U21") (pin "19") (pinfunction "OE#_19") (pintype "unspecified"))
      (node (ref "U23") (pin "4") (pinfunction "GND_4") (pintype "unspecified"))
      (node (ref "U26") (pin "2") (pinfunction "GND_2") (pintype "unspecified"))
      (node (ref "U27") (pin "11") (pinfunction "EXP_11") (pintype "input"))
      (node (ref "U27") (pin "3") (pinfunction "GND_3") (pintype "input"))
      (node (ref "U27") (pin "9") (pinfunction "GND_9") (pintype "input"))
      (node (ref "U8") (pin "4") (pinfunction "GND_4") (pintype "unspecified"))
      (node (ref "U9") (pin "1") (pinfunction "1_1") (pintype "unspecified"))
      (node (ref "USB1") (pin "1") (pinfunction "GND_1") (pintype "unspecified"))
      (node (ref "USB1") (pin "12") (pinfunction "GND_12") (pintype "unspecified"))
      (node (ref "USB1") (pin "13") (pinfunction "SHELL_13") (pintype "unspecified"))
      (node (ref "USB1") (pin "14") (pinfunction "SHELL_14") (pintype "unspecified"))
    )
    (net (code "25") (name "GPIO2") (class "Default")
      (node (ref "R28") (pin "2") (pinfunction "2_2") (pintype "input"))
      (node (ref "U13") (pin "4") (pinfunction "GPIO2_4") (pintype "bidirectional"))
    )
    (net (code "26") (name "GPIO3") (class "Default")
      (node (ref "C25") (pin "2") (pinfunction "2_2") (pintype "input"))
      (node (ref "SW2") (pin "1") (pinfunction "1_1") (pintype "input"))
      (node (ref "U13") (pin "5") (pinfunction "GPIO3_5") (pintype "bidirectional"))
    )
    (net (code "27") (name "GPIO4") (class "Default")
      (node (ref "H1") (pin "3") (pinfunction "3_3") (pintype "unspecified"))
      (node (ref "U13") (pin "6") (pinfunction "GPIO4_6") (pintype "bidirectional"))
    )
    (net (code "28") (name "GPIO5") (class "Default")
      (node (ref "H1") (pin "2") (pinfunction "2_2") (pintype "unspecified"))
      (node (ref "U13") (pin "7") (pinfunction "GPIO5_7") (pintype "bidirectional"))
    )
    (net (code "29") (name "GPIO6") (class "Default")
      (node (ref "C26") (pin "2") (pinfunction "2_2") (pintype "input"))
      (node (ref "SW3") (pin "1") (pinfunction "1_1") (pintype "input"))
      (node (ref "U13") (pin "8") (pinfunction "GPIO6_8") (pintype "bidirectional"))
    )
    (net (code "30") (name "GPIO7") (class "Default")
      (node (ref "FPC1") (pin "1") (pinfunction "1_1") (pintype "unspecified"))
      (node (ref "H3") (pin "3") (pinfunction "3_3") (pintype "unspecified"))
      (node (ref "U13") (pin "9") (pinfunction "GPIO7_9") (pintype "bidirectional"))
    )
    (net (code "31") (name "GPIO8") (class "Default")
      (node (ref "FPC1") (pin "3") (pinfunction "3_3") (pintype "unspecified"))
      (node (ref "H3") (pin "4") (pinfunction "4_4") (pintype "unspecified"))
      (node (ref "U13") (pin "11") (pinfunction "GPIO8_11") (pintype "bidirectional"))
    )
    (net (code "32") (name "GPIO9") (class "Default")
      (node (ref "FPC1") (pin "5") (pinfunction "5_5") (pintype "unspecified"))
      (node (ref "H3") (pin "5") (pinfunction "5_5") (pintype "unspecified"))
      (node (ref "U13") (pin "12") (pinfunction "GPIO9_12") (pintype "bidirectional"))
    )
    (net (code "33") (name "GPIO10") (class "Default")
      (node (ref "FPC1") (pin "7") (pinfunction "7_7") (pintype "unspecified"))
      (node (ref "H3") (pin "6") (pinfunction "6_6") (pintype "unspecified"))
      (node (ref "U13") (pin "13") (pinfunction "GPIO10_13") (pintype "bidirectional"))
      (node (ref "U26") (pin "5") (pinfunction "A1_5") (pintype "unspecified"))
    )
    (net (code "34") (name "GPIO11") (class "Default")
      (node (ref "FPC1") (pin "9") (pinfunction "9_9") (pintype "unspecified"))
      (node (ref "H3") (pin "7") (pinfunction "7_7") (pintype "unspecified"))
      (node (ref "U13") (pin "14") (pinfunction "GPIO11_14") (pintype "bidirectional"))
      (node (ref "U26") (pin "4") (pinfunction "A2_4") (pintype "unspecified"))
    )
    (net (code "35") (name "GPIO14") (class "Default")
      (node (ref "U13") (pin "17") (pinfunction "GPIO14_17") (pintype "bidirectional"))
      (node (ref "U21") (pin "8") (pinfunction "A7_8") (pintype "unspecified"))
    )
    (net (code "36") (name "GPIO15") (class "Default")
      (node (ref "U13") (pin "18") (pinfunction "GPIO15_18") (pintype "bidirectional"))
      (node (ref "U21") (pin "7") (pinfunction "A6_7") (pintype "unspecified"))
    )
    (net (code "37") (name "GPIO16") (class "Default")
      (node (ref "U13") (pin "27") (pinfunction "GPIO16_27") (pintype "bidirectional"))
      (node (ref "U21") (pin "6") (pinfunction "A5_6") (pintype "unspecified"))
    )
    (net (code "38") (name "GPIO17") (class "Default")
      (node (ref "U13") (pin "28") (pinfunction "GPIO17_28") (pintype "bidirectional"))
      (node (ref "U21") (pin "5") (pinfunction "A4_5") (pintype "unspecified"))
    )
    (net (code "39") (name "GPIO18") (class "Default")
      (node (ref "U13") (pin "29") (pinfunction "GPIO18_29") (pintype "bidirectional"))
      (node (ref "U21") (pin "4") (pinfunction "A3_4") (pintype "unspecified"))
    )
    (net (code "40") (name "GPIO19") (class "Default")
      (node (ref "U13") (pin "30") (pinfunction "GPIO19_30") (pintype "bidirectional"))
      (node (ref "U21") (pin "3") (pinfunction "A2_3") (pintype "unspecified"))
    )
    (net (code "41") (name "GPIO20") (class "Default")
      (node (ref "U13") (pin "31") (pinfunction "GPIO20_31") (pintype "bidirectional"))
      (node (ref "U21") (pin "2") (pinfunction "A1_2") (pintype "unspecified"))
    )
    (net (code "42") (name "GPIO21") (class "Default")
      (node (ref "U13") (pin "32") (pinfunction "GPIO21_32") (pintype "bidirectional"))
      (node (ref "U17") (pin "9") (pinfunction "A8_9") (pintype "unspecified"))
    )
    (net (code "43") (name "GPIO22") (class "Default")
      (node (ref "U13") (pin "34") (pinfunction "GPIO22_34") (pintype "bidirectional"))
      (node (ref "U17") (pin "8") (pinfunction "A7_8") (pintype "unspecified"))
    )
    (net (code "44") (name "GPIO23") (class "Default")
      (node (ref "U13") (pin "35") (pinfunction "GPIO23_35") (pintype "bidirectional"))
      (node (ref "U17") (pin "7") (pinfunction "A6_7") (pintype "unspecified"))
    )
    (net (code "45") (name "GPIO24") (class "Default")
      (node (ref "U13") (pin "36") (pinfunction "GPIO24_36") (pintype "bidirectional"))
      (node (ref "U17") (pin "6") (pinfunction "A5_6") (pintype "unspecified"))
    )
    (net (code "46") (name "GPIO25") (class "Default")
      (node (ref "U13") (pin "37") (pinfunction "GPIO25_37") (pintype "bidirectional"))
      (node (ref "U17") (pin "5") (pinfunction "A4_5") (pintype "unspecified"))
    )
    (net (code "47") (name "GPIO26_ADC0") (class "Default")
      (node (ref "U13") (pin "38") (pinfunction "GPIO26_ADC0_38") (pintype "bidirectional"))
      (node (ref "U17") (pin "4") (pinfunction "A3_4") (pintype "unspecified"))
    )
    (net (code "48") (name "GPIO27_ADC1") (class "Default")
      (node (ref "U13") (pin "39") (pinfunction "GPIO27_ADC1_39") (pintype "bidirectional"))
      (node (ref "U17") (pin "3") (pinfunction "A2_3") (pintype "unspecified"))
    )
    (net (code "49") (name "GPIO28_ADC2") (class "Default")
      (node (ref "U13") (pin "40") (pinfunction "GPIO28_ADC2_40") (pintype "bidirectional"))
      (node (ref "U17") (pin "2") (pinfunction "A1_2") (pintype "unspecified"))
    )
    (net (code "50") (name "GPIO29_ADC3") (class "Default")
      (node (ref "R29") (pin "2") (pinfunction "2_2") (pintype "input"))
      (node (ref "U13") (pin "41") (pinfunction "GPIO29_ADC3_41") (pintype "bidirectional"))
    )
    (net (code "51") (name "INPUT_HI") (class "Default")
      (node (ref "R10") (pin "1") (pinfunction "1_1") (pintype "unspecified"))
      (node (ref "U24") (pin "13") (pinfunction "X_13") (pintype "unspecified"))
      (node (ref "U24") (pin "3") (pinfunction "Y_3") (pintype "unspecified"))
    )
    (net (code "52") (name "Net-(C18-Pad1)") (class "Default")
      (node (ref "C18") (pin "1") (pinfunction "1_1") (pintype "input"))
      (node (ref "R12") (pin "2") (pinfunction "2_2") (pintype "unspecified"))
      (node (ref "R13") (pin "1") (pinfunction "1_1") (pintype "unspecified"))
      (node (ref "R14") (pin "2") (pinfunction "2_2") (pintype "unspecified"))
    )
    (net (code "53") (name "Net-(D4-K)") (class "Default")
      (node (ref "C29") (pin "2") (pinfunction "2_2") (pintype "input"))
      (node (ref "D4") (pin "1") (pinfunction "K_1") (pintype "unspecified"))
      (node (ref "D5") (pin "1") (pinfunction "K_1") (pintype "unspecified"))
      (node (ref "R27") (pin "2") (pinfunction "2_2") (pintype "input"))
      (node (ref "U27") (pin "5") (pinfunction "VIN_5") (pintype "input"))
      (node (ref "U27") (pin "8") (pinfunction "VINA_8") (pintype "input"))
    )
    (net (code "54") (name "Net-(D5-A)") (class "Default")
      (node (ref "D5") (pin "2") (pinfunction "A_2") (pintype "unspecified"))
      (node (ref "USB1") (pin "11") (pinfunction "VBUS_11") (pintype "unspecified"))
      (node (ref "USB1") (pin "2") (pinfunction "VBUS_2") (pintype "unspecified"))
    )
    (net (code "55") (name "Net-(LED1-+)") (class "Default")
      (node (ref "LED1") (pin "2") (pinfunction "+_2") (pintype "unspecified"))
      (node (ref "R28") (pin "1") (pinfunction "1_1") (pintype "input"))
    )
    (net (code "56") (name "Net-(LED2-+)") (class "Default")
      (node (ref "LED2") (pin "2") (pinfunction "+_2") (pintype "unspecified"))
      (node (ref "R29") (pin "1") (pinfunction "1_1") (pintype "input"))
    )
    (net (code "57") (name "Net-(LED3-A)") (class "Default")
      (node (ref "LED3") (pin "2") (pinfunction "A_2") (pintype "input"))
      (node (ref "R30") (pin "2") (pinfunction "2_2") (pintype "input"))
    )
    (net (code "58") (name "Net-(R11-Pad2)") (class "Default")
      (node (ref "R11") (pin "2") (pinfunction "2_2") (pintype "input"))
      (node (ref "U18") (pin "2") (pinfunction "2_2") (pintype "unspecified"))
      (node (ref "U19") (pin "2") (pinfunction "2_2") (pintype "unspecified"))
    )
    (net (code "59") (name "Net-(R14-Pad1)") (class "Default")
      (node (ref "R14") (pin "1") (pinfunction "1_1") (pintype "unspecified"))
      (node (ref "R15") (pin "1") (pinfunction "1_1") (pintype "input"))
    )
    (net (code "60") (name "Net-(R16-Pad1)") (class "Default")
      (node (ref "R16") (pin "1") (pinfunction "1_1") (pintype "input"))
      (node (ref "R17") (pin "1") (pinfunction "1_1") (pintype "input"))
      (node (ref "SW1") (pin "2") (pinfunction "2_2") (pintype "input"))
    )
    (net (code "61") (name "Net-(U1--IN)") (class "Default")
      (node (ref "R1") (pin "1") (pinfunction "1_1") (pintype "unspecified"))
      (node (ref "R2") (pin "2") (pinfunction "2_2") (pintype "unspecified"))
      (node (ref "U1") (pin "2") (pinfunction "-IN_2") (pintype "unspecified"))
    )
    (net (code "62") (name "Net-(U2-+IN)") (class "Default")
      (node (ref "D2") (pin "1") (pinfunction "1_1") (pintype "unspecified"))
      (node (ref "R3") (pin "1") (pinfunction "1_1") (pintype "unspecified"))
      (node (ref "R4") (pin "2") (pinfunction "2_2") (pintype "unspecified"))
      (node (ref "U2") (pin "3") (pinfunction "+IN_3") (pintype "unspecified"))
    )
    (net (code "63") (name "Net-(U7-+IN)") (class "Default")
      (node (ref "D3") (pin "1") (pinfunction "1_1") (pintype "unspecified"))
      (node (ref "R6") (pin "1") (pinfunction "1_1") (pintype "unspecified"))
      (node (ref "R7") (pin "2") (pinfunction "2_2") (pintype "unspecified"))
      (node (ref "U7") (pin "3") (pinfunction "+IN_3") (pintype "unspecified"))
    )
    (net (code "64") (name "Net-(U12-AUTO-ZERO)") (class "Default")
      (node (ref "U12") (pin "31") (pinfunction "AUTO-ZERO_31") (pintype "unspecified"))
      (node (ref "U18") (pin "1") (pinfunction "1_1") (pintype "unspecified"))
    )
    (net (code "65") (name "Net-(U12-BUFFER)") (class "Default")
      (node (ref "R11") (pin "1") (pinfunction "1_1") (pintype "input"))
      (node (ref "U12") (pin "30") (pinfunction "BUFFER_30") (pintype "unspecified"))
    )
    (net (code "66") (name "Net-(U12-INPUT_HI)") (class "Default")
      (node (ref "R10") (pin "2") (pinfunction "2_2") (pintype "unspecified"))
      (node (ref "U12") (pin "35") (pinfunction "INPUT_HI_35") (pintype "unspecified"))
      (node (ref "U16") (pin "1") (pinfunction "1_1") (pintype "unspecified"))
    )
    (net (code "67") (name "Net-(U12-INTEGRATOR)") (class "Default")
      (node (ref "U12") (pin "32") (pinfunction "INTEGRATOR_32") (pintype "unspecified"))
      (node (ref "U19") (pin "1") (pinfunction "1_1") (pintype "unspecified"))
    )
    (net (code "68") (name "Net-(U12-OSC_IN)") (class "Default")
      (node (ref "U12") (pin "22") (pinfunction "OSC_IN_22") (pintype "unspecified"))
      (node (ref "X1") (pin "1") (pinfunction "OSC1_1") (pintype "input"))
    )
    (net (code "69") (name "Net-(U12-OSC_OUT)") (class "Default")
      (node (ref "U12") (pin "23") (pinfunction "OSC_OUT_23") (pintype "unspecified"))
      (node (ref "X1") (pin "2") (pinfunction "OSC2_2") (pintype "input"))
    )
    (net (code "70") (name "Net-(U12-REF_CAP+)") (class "Default")
      (node (ref "U12") (pin "37") (pinfunction "REF_CAP+_37") (pintype "unspecified"))
      (node (ref "U15") (pin "1") (pinfunction "1_1") (pintype "unspecified"))
    )
    (net (code "71") (name "Net-(U12-REF_CAP-)") (class "Default")
      (node (ref "U12") (pin "38") (pinfunction "REF_CAP-_38") (pintype "unspecified"))
      (node (ref "U15") (pin "2") (pinfunction "2_2") (pintype "unspecified"))
    )
    (net (code "72") (name "Net-(U13-USB_DM)") (class "Default")
      (node (ref "R9") (pin "2") (pinfunction "2_2") (pintype "input"))
      (node (ref "U13") (pin "46") (pinfunction "USB_DM_46") (pintype "bidirectional"))
    )
    (net (code "73") (name "Net-(U13-USB_DP)") (class "Default")
      (node (ref "R8") (pin "2") (pinfunction "2_2") (pintype "input"))
      (node (ref "U13") (pin "47") (pinfunction "USB_DP_47") (pintype "bidirectional"))
    )
    (net (code "74") (name "Net-(U14-CFLY+)") (class "Default")
      (node (ref "C14") (pin "2") (pinfunction "2_2") (pintype "input"))
      (node (ref "U14") (pin "5") (pinfunction "CFLY+_5") (pintype "unspecified"))
    )
    (net (code "75") (name "Net-(U14-CFLY-)") (class "Default")
      (node (ref "C14") (pin "1") (pinfunction "1_1") (pintype "input"))
      (node (ref "U14") (pin "3") (pinfunction "CFLY-_3") (pintype "unspecified"))
    )
    (net (code "76") (name "Net-(U20-VOUT)") (class "Default")
      (node (ref "R12") (pin "1") (pinfunction "1_1") (pintype "unspecified"))
      (node (ref "U20") (pin "6") (pinfunction "VOUT_6") (pintype "unspecified"))
    )
    (net (code "77") (name "Net-(U27-EN)") (class "Default")
      (node (ref "R27") (pin "1") (pinfunction "1_1") (pintype "input"))
      (node (ref "U27") (pin "6") (pinfunction "EN_6") (pintype "input"))
    )
    (net (code "78") (name "Net-(U27-FB)") (class "Default")
      (node (ref "R25") (pin "2") (pinfunction "2_2") (pintype "input"))
      (node (ref "R26") (pin "1") (pinfunction "1_1") (pintype "input"))
      (node (ref "U27") (pin "10") (pinfunction "FB_10") (pintype "input"))
    )
    (net (code "79") (name "Net-(U27-LX1)") (class "Default")
      (node (ref "U27") (pin "4") (pinfunction "LX1_4") (pintype "input"))
      (node (ref "U28") (pin "1") (pinfunction "1_1") (pintype "unspecified"))
    )
    (net (code "80") (name "Net-(U27-LX2)") (class "Default")
      (node (ref "U27") (pin "2") (pinfunction "LX2_2") (pintype "input"))
      (node (ref "U28") (pin "2") (pinfunction "2_2") (pintype "unspecified"))
    )
    (net (code "81") (name "Net-(X2-OSC2)") (class "Default")
      (node (ref "C22") (pin "1") (pinfunction "1_1") (pintype "input"))
      (node (ref "R18") (pin "2") (pinfunction "2_2") (pintype "input"))
      (node (ref "X2") (pin "3") (pinfunction "OSC2_3") (pintype "unspecified"))
    )
    (net (code "82") (name "OR") (class "Default")
      (node (ref "U12") (pin "4") (pinfunction "OR_4") (pintype "unspecified"))
      (node (ref "U21") (pin "14") (pinfunction "B5_14") (pintype "unspecified"))
    )
    (net (code "83") (name "POL") (class "Default")
      (node (ref "U12") (pin "3") (pinfunction "POL_3") (pintype "unspecified"))
      (node (ref "U21") (pin "13") (pinfunction "B6_13") (pintype "unspecified"))
    )
    (net (code "84") (name "QSPI_SCLK") (class "Default")
      (node (ref "U13") (pin "52") (pinfunction "QSPI_SCLK_52") (pintype "output"))
      (node (ref "U23") (pin "6") (pinfunction "CLK_6") (pintype "unspecified"))
    )
    (net (code "85") (name "QSPI_SD0") (class "Default")
      (node (ref "U13") (pin "53") (pinfunction "QSPI_SD0_53") (pintype "bidirectional"))
      (node (ref "U23") (pin "5") (pinfunction "DI/IO0_5") (pintype "unspecified"))
    )
    (net (code "86") (name "QSPI_SD1") (class "Default")
      (node (ref "U13") (pin "55") (pinfunction "QSPI_SD1_55") (pintype "bidirectional"))
      (node (ref "U23") (pin "2") (pinfunction "DO/IO1_2") (pintype "unspecified"))
    )
    (net (code "87") (name "QSPI_SD2") (class "Default")
      (node (ref "U13") (pin "54") (pinfunction "QSPI_SD2_54") (pintype "bidirectional"))
      (node (ref "U23") (pin "3") (pinfunction "IO2_3") (pintype "unspecified"))
    )
    (net (code "88") (name "QSPI_SD3") (class "Default")
      (node (ref "U13") (pin "51") (pinfunction "QSPI_SD3_51") (pintype "bidirectional"))
      (node (ref "U23") (pin "7") (pinfunction "IO3_7") (pintype "unspecified"))
    )
    (net (code "89") (name "QSPI_SS") (class "Default")
      (node (ref "R17") (pin "2") (pinfunction "2_2") (pintype "input"))
      (node (ref "U13") (pin "56") (pinfunction "QSPI_SS_56") (pintype "bidirectional"))
      (node (ref "U23") (pin "1") (pinfunction "/CS_1") (pintype "unspecified"))
    )
    (net (code "90") (name "REF_IN+") (class "Default")
      (node (ref "R13") (pin "2") (pinfunction "2_2") (pintype "unspecified"))
      (node (ref "U12") (pin "36") (pinfunction "REF_IN+_36") (pintype "unspecified"))
    )
    (net (code "91") (name "RUN") (class "Default")
      (node (ref "U13") (pin "26") (pinfunction "RUN_26") (pintype "input"))
    )
    (net (code "92") (name "RX") (class "Default")
      (node (ref "H6") (pin "2") (pinfunction "2_2") (pintype "unspecified"))
      (node (ref "U13") (pin "3") (pinfunction "GPIO1_3") (pintype "bidirectional"))
    )
    (net (code "93") (name "SCL0") (class "Default")
      (node (ref "FPC1") (pin "8") (pinfunction "8_8") (pintype "unspecified"))
      (node (ref "H5") (pin "3") (pinfunction "3_3") (pintype "unspecified"))
      (node (ref "R21") (pin "2") (pinfunction "2_2") (pintype "input"))
      (node (ref "U13") (pin "16") (pinfunction "GPIO13_16") (pintype "bidirectional"))
    )
    (net (code "94") (name "SDA0") (class "Default")
      (node (ref "FPC1") (pin "6") (pinfunction "6_6") (pintype "unspecified"))
      (node (ref "H5") (pin "4") (pinfunction "4_4") (pintype "unspecified"))
      (node (ref "R22") (pin "2") (pinfunction "2_2") (pintype "input"))
      (node (ref "U13") (pin "15") (pinfunction "GPIO12_15") (pintype "bidirectional"))
    )
    (net (code "95") (name "STATUS") (class "Default")
      (node (ref "U12") (pin "2") (pinfunction "STATUS_2") (pintype "unspecified"))
      (node (ref "U21") (pin "12") (pinfunction "B7_12") (pintype "unspecified"))
    )
    (net (code "96") (name "SWCLK") (class "Default")
      (node (ref "U13") (pin "24") (pinfunction "SWCLK_24") (pintype "output"))
    )
    (net (code "97") (name "SWDIO") (class "Default")
      (node (ref "U13") (pin "25") (pinfunction "SWD_25") (pintype "bidirectional"))
    )
    (net (code "98") (name "TX") (class "Default")
      (node (ref "H6") (pin "3") (pinfunction "3_3") (pintype "unspecified"))
      (node (ref "U13") (pin "2") (pinfunction "GPIO0_2") (pintype "bidirectional"))
    )
    (net (code "99") (name "USB_DM") (class "Default")
      (node (ref "R9") (pin "1") (pinfunction "1_1") (pintype "input"))
      (node (ref "USB1") (pin "5") (pinfunction "DN2_5") (pintype "unspecified"))
      (node (ref "USB1") (pin "7") (pinfunction "DN1_7") (pintype "unspecified"))
    )
    (net (code "100") (name "USB_DP") (class "Default")
      (node (ref "R8") (pin "1") (pinfunction "1_1") (pintype "input"))
      (node (ref "USB1") (pin "6") (pinfunction "DP1_6") (pintype "unspecified"))
      (node (ref "USB1") (pin "8") (pinfunction "DP2_8") (pintype "unspecified"))
    )
    (net (code "101") (name "V2_DIV") (class "Default")
      (node (ref "H4") (pin "2") (pinfunction "2_2") (pintype "unspecified"))
      (node (ref "R3") (pin "2") (pinfunction "2_2") (pintype "unspecified"))
    )
    (net (code "102") (name "V2_INPUT_HI") (class "Default")
      (node (ref "U2") (pin "2") (pinfunction "-IN_2") (pintype "unspecified"))
      (node (ref "U2") (pin "6") (pinfunction "OUT_6") (pintype "unspecified"))
      (node (ref "U24") (pin "2") (pinfunction "Y2_2") (pintype "unspecified"))
    )
    (net (code "103") (name "VIN") (class "Default")
      (node (ref "C1") (pin "1") (pinfunction "1_1") (pintype "input"))
      (node (ref "C17") (pin "1") (pinfunction "1_1") (pintype "input"))
      (node (ref "CN1") (pin "1") (pinfunction "1_1") (pintype "unspecified"))
      (node (ref "H2") (pin "7") (pinfunction "7_7") (pintype "unspecified"))
      (node (ref "U20") (pin "2") (pinfunction "VIN_2") (pintype "unspecified"))
      (node (ref "U8") (pin "1") (pinfunction "IN_1") (pintype "unspecified"))
    )
    (net (code "104") (name "V_DIV") (class "Default")
      (node (ref "CN2") (pin "1") (pinfunction "1_1") (pintype "unspecified"))
      (node (ref "H2") (pin "5") (pinfunction "5_5") (pintype "unspecified"))
      (node (ref "R6") (pin "2") (pinfunction "2_2") (pintype "unspecified"))
    )
    (net (code "105") (name "V_INPUT_HI") (class "Default")
      (node (ref "U24") (pin "5") (pinfunction "Y1_5") (pintype "unspecified"))
      (node (ref "U7") (pin "2") (pinfunction "-IN_2") (pintype "unspecified"))
      (node (ref "U7") (pin "6") (pinfunction "OUT_6") (pintype "unspecified"))
    )
    (net (code "106") (name "X0") (class "Default")
      (node (ref "H4") (pin "5") (pinfunction "5_5") (pintype "unspecified"))
      (node (ref "U24") (pin "12") (pinfunction "X0_12") (pintype "unspecified"))
    )
    (net (code "107") (name "X1") (class "Default")
      (node (ref "H4") (pin "6") (pinfunction "6_6") (pintype "unspecified"))
      (node (ref "U24") (pin "14") (pinfunction "X1_14") (pintype "unspecified"))
    )
    (net (code "108") (name "X2") (class "Default")
      (node (ref "H4") (pin "7") (pinfunction "7_7") (pintype "unspecified"))
      (node (ref "U24") (pin "15") (pinfunction "X2_15") (pintype "unspecified"))
    )
    (net (code "109") (name "X3") (class "Default")
      (node (ref "H4") (pin "4") (pinfunction "4_4") (pintype "unspecified"))
      (node (ref "U24") (pin "11") (pinfunction "X3_11") (pintype "unspecified"))
    )
    (net (code "110") (name "XIN") (class "Default")
      (node (ref "C27") (pin "1") (pinfunction "1_1") (pintype "input"))
      (node (ref "R19") (pin "1") (pinfunction "1_1") (pintype "input"))
      (node (ref "U13") (pin "20") (pinfunction "XIN_20") (pintype "input"))
      (node (ref "X2") (pin "1") (pinfunction "OSC1_1") (pintype "unspecified"))
    )
    (net (code "111") (name "XOUT") (class "Default")
      (node (ref "R18") (pin "1") (pinfunction "1_1") (pintype "input"))
      (node (ref "R19") (pin "2") (pinfunction "2_2") (pintype "input"))
      (node (ref "U13") (pin "21") (pinfunction "XOUT_21") (pintype "unspecified"))
    )
    (net (code "112") (name "Y3") (class "Default")
      (node (ref "H4") (pin "3") (pinfunction "3_3") (pintype "unspecified"))
      (node (ref "U24") (pin "4") (pinfunction "Y3_4") (pintype "unspecified"))
    )
    (net (code "113") (name "unconnected-(FPC1-Pad10)") (class "Default")
      (node (ref "FPC1") (pin "10") (pinfunction "10_10") (pintype "unspecified"))
    )
    (net (code "114") (name "unconnected-(FPC1-Pad13)") (class "Default")
      (node (ref "FPC1") (pin "13") (pinfunction "13_13") (pintype "unspecified"))
    )
    (net (code "115") (name "unconnected-(FPC1-Pad14)") (class "Default")
      (node (ref "FPC1") (pin "14") (pinfunction "14_14") (pintype "unspecified"))
    )
    (net (code "116") (name "unconnected-(H7-Pad2)") (class "Default")
      (node (ref "H7") (pin "2") (pinfunction "2_2") (pintype "unspecified"))
    )
    (net (code "117") (name "unconnected-(SW2-Pad3)") (class "Default")
      (node (ref "SW2") (pin "3") (pinfunction "3_3") (pintype "input"))
    )
    (net (code "118") (name "unconnected-(SW2-Pad4)") (class "Default")
      (node (ref "SW2") (pin "4") (pinfunction "4_4") (pintype "input"))
    )
    (net (code "119") (name "unconnected-(SW2-Pad5)") (class "Default")
      (node (ref "SW2") (pin "5") (pinfunction "5_5") (pintype "input"))
    )
    (net (code "120") (name "unconnected-(SW3-Pad3)") (class "Default")
      (node (ref "SW3") (pin "3") (pinfunction "3_3") (pintype "input"))
    )
    (net (code "121") (name "unconnected-(SW3-Pad4)") (class "Default")
      (node (ref "SW3") (pin "4") (pinfunction "4_4") (pintype "input"))
    )
    (net (code "122") (name "unconnected-(SW3-Pad5)") (class "Default")
      (node (ref "SW3") (pin "5") (pinfunction "5_5") (pintype "input"))
    )
    (net (code "123") (name "unconnected-(U1-OVER_COMP-Pad5)") (class "Default")
      (node (ref "U1") (pin "5") (pinfunction "OVER_COMP_5") (pintype "unspecified"))
    )
    (net (code "124") (name "unconnected-(U1-VOS_TRIM-Pad1)") (class "Default")
      (node (ref "U1") (pin "1") (pinfunction "VOS_TRIM_1") (pintype "unspecified"))
    )
    (net (code "125") (name "unconnected-(U1-VOS_TRIM-Pad8)") (class "Default")
      (node (ref "U1") (pin "8") (pinfunction "VOS_TRIM_8") (pintype "unspecified"))
    )
    (net (code "126") (name "unconnected-(U2-OVER_COMP-Pad5)") (class "Default")
      (node (ref "U2") (pin "5") (pinfunction "OVER_COMP_5") (pintype "unspecified"))
    )
    (net (code "127") (name "unconnected-(U2-VOS_TRIM-Pad1)") (class "Default")
      (node (ref "U2") (pin "1") (pinfunction "VOS_TRIM_1") (pintype "unspecified"))
    )
    (net (code "128") (name "unconnected-(U2-VOS_TRIM-Pad8)") (class "Default")
      (node (ref "U2") (pin "8") (pinfunction "VOS_TRIM_8") (pintype "unspecified"))
    )
    (net (code "129") (name "unconnected-(U7-OVER_COMP-Pad5)") (class "Default")
      (node (ref "U7") (pin "5") (pinfunction "OVER_COMP_5") (pintype "unspecified"))
    )
    (net (code "130") (name "unconnected-(U7-VOS_TRIM-Pad1)") (class "Default")
      (node (ref "U7") (pin "1") (pinfunction "VOS_TRIM_1") (pintype "unspecified"))
    )
    (net (code "131") (name "unconnected-(U7-VOS_TRIM-Pad8)") (class "Default")
      (node (ref "U7") (pin "8") (pinfunction "VOS_TRIM_8") (pintype "unspecified"))
    )
    (net (code "132") (name "unconnected-(U12-BUF_OSC_OUT-Pad25)") (class "Default")
      (node (ref "U12") (pin "25") (pinfunction "BUF_OSC_OUT_25") (pintype "unspecified"))
    )
    (net (code "133") (name "unconnected-(U12-REF_OUT-Pad29)") (class "Default")
      (node (ref "U12") (pin "29") (pinfunction "REF_OUT_29") (pintype "unspecified"))
    )
    (net (code "134") (name "unconnected-(U20-DNC-Pad1)") (class "Default")
      (node (ref "U20") (pin "1") (pinfunction "DNC_1") (pintype "unspecified"))
    )
    (net (code "135") (name "unconnected-(U20-DNC-Pad3)") (class "Default")
      (node (ref "U20") (pin "3") (pinfunction "DNC_3") (pintype "unspecified"))
    )
    (net (code "136") (name "unconnected-(U20-DNC-Pad7)") (class "Default")
      (node (ref "U20") (pin "7") (pinfunction "DNC_7") (pintype "unspecified"))
    )
    (net (code "137") (name "unconnected-(U20-DNC-Pad8)") (class "Default")
      (node (ref "U20") (pin "8") (pinfunction "DNC_8") (pintype "unspecified"))
    )
    (net (code "138") (name "unconnected-(U20-TRIM-Pad5)") (class "Default")
      (node (ref "U20") (pin "5") (pinfunction "TRIM_5") (pintype "unspecified"))
    )
    (net (code "139") (name "unconnected-(U21-A8-Pad9)") (class "Default")
      (node (ref "U21") (pin "9") (pinfunction "A8_9") (pintype "unspecified"))
    )
    (net (code "140") (name "unconnected-(U21-B8-Pad11)") (class "Default")
      (node (ref "U21") (pin "11") (pinfunction "B8_11") (pintype "unspecified"))
    )
    (net (code "141") (name "unconnected-(U27-PS-Pad7)") (class "Default")
      (node (ref "U27") (pin "7") (pinfunction "PS_7") (pintype "input"))
    )
    (net (code "142") (name "unconnected-(USB1-SBU1-Pad9)") (class "Default")
      (node (ref "USB1") (pin "9") (pinfunction "SBU1_9") (pintype "unspecified"))
    )
    (net (code "143") (name "unconnected-(USB1-SBU2-Pad3)") (class "Default")
      (node (ref "USB1") (pin "3") (pinfunction "SBU2_3") (pintype "unspecified"))
    )
    (net (code "144") (name "unconnected-(X2-GND-Pad2)") (class "Default")
      (node (ref "X2") (pin "2") (pinfunction "GND_2") (pintype "unspecified"))
    )
    (net (code "145") (name "unconnected-(X2-GND-Pad4)") (class "Default")
      (node (ref "X2") (pin "4") (pinfunction "GND_4") (pintype "unspecified"))
    )
  )
)
